# Vorlage_ATmega2560-16AU.net
KiCad netlist of a schematic drawn in EAGLE
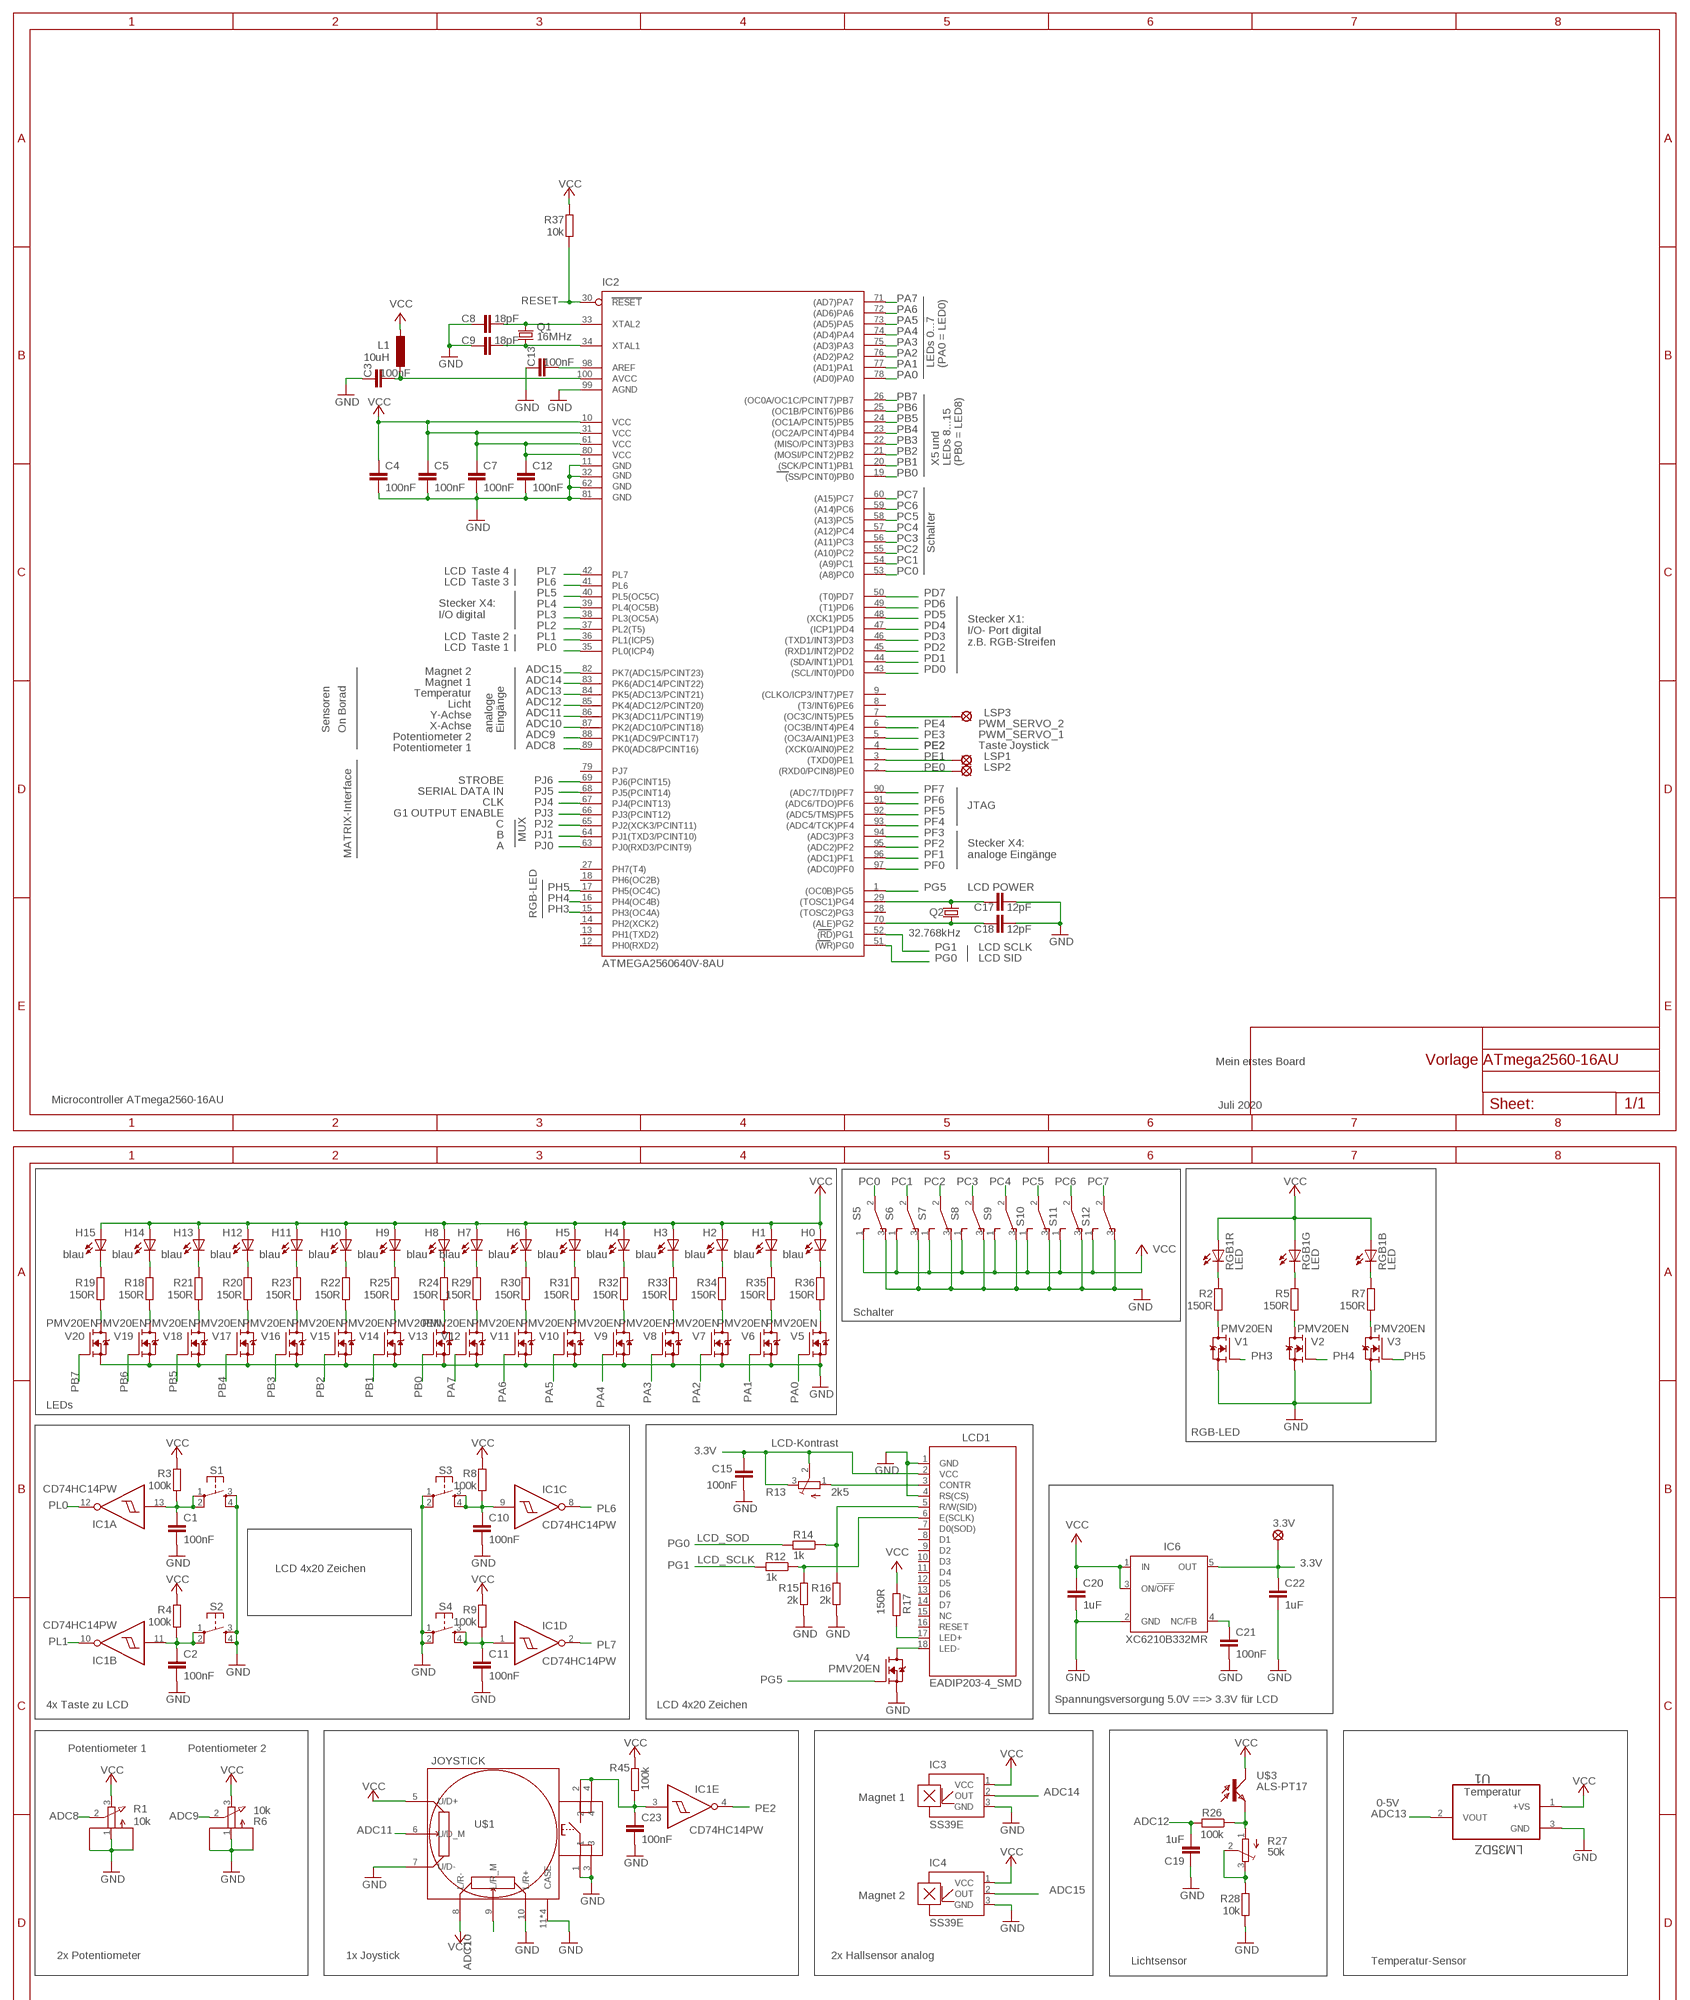
[diagram p0: schematic, sheet 1, part 1 of 2]
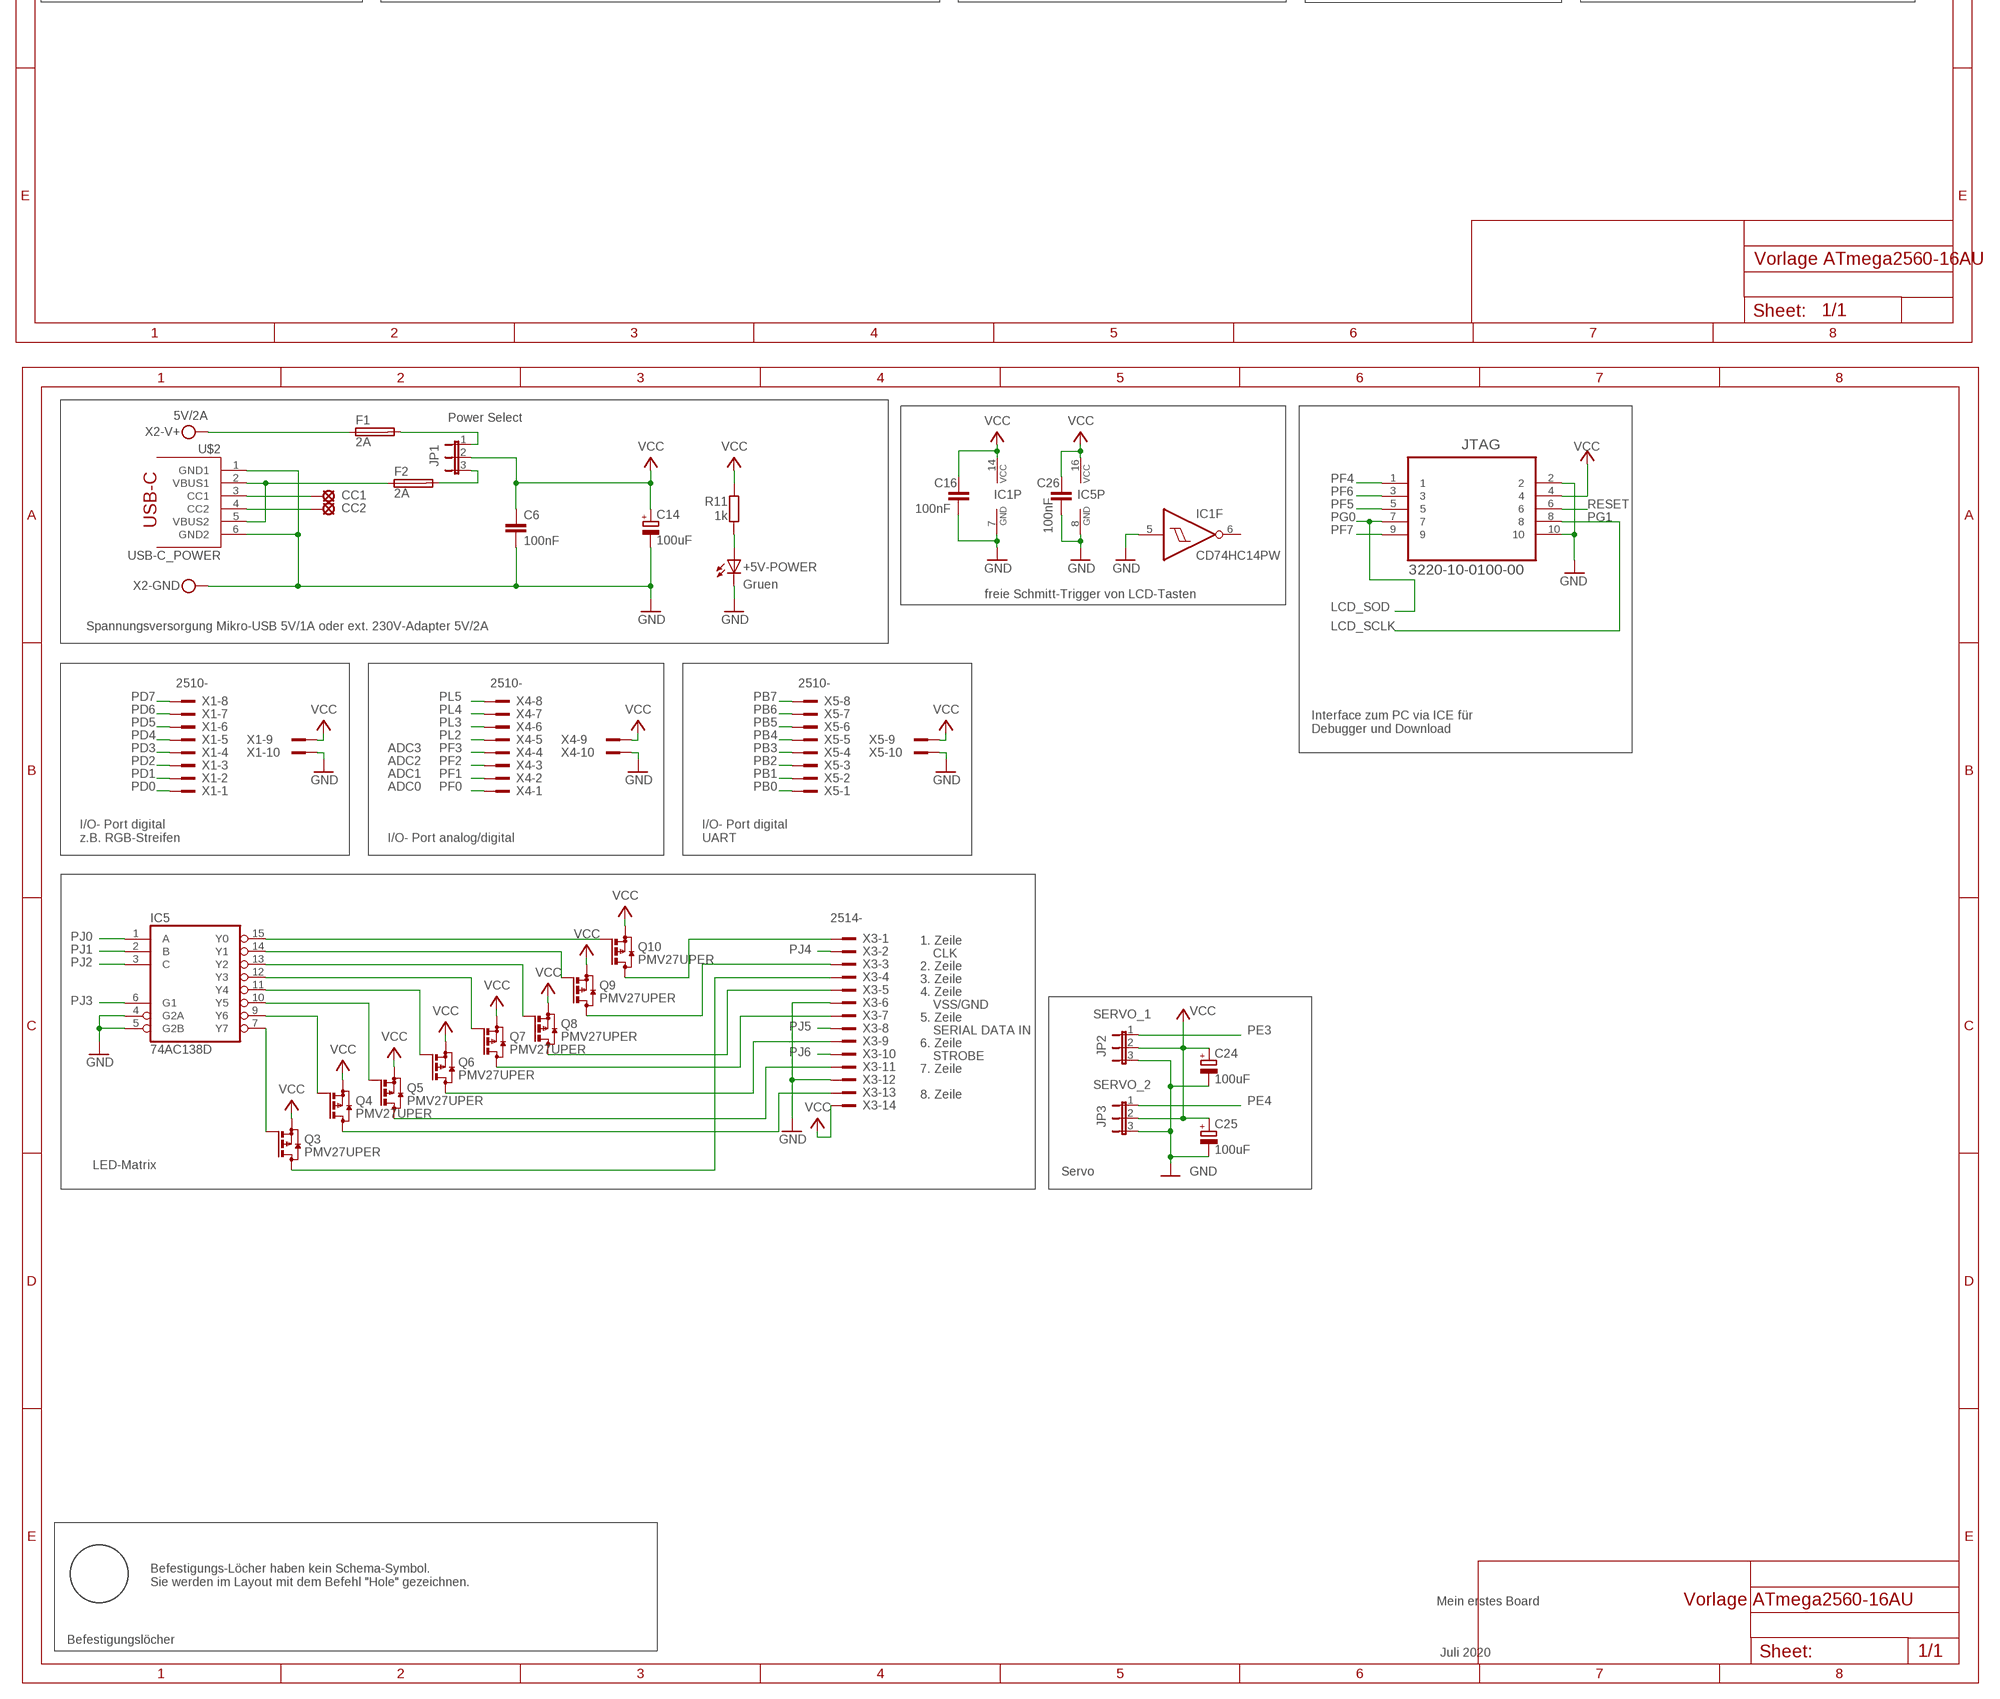
[diagram p1: schematic, sheet 1, part 2 of 2]

(export (version "E")
  (design (tool "Eeschema 10.0.6"))
  (components
    (comp (ref "+5V-POWER")
      (value "Gruen")
      (footprint "eagle-import:CHIPLED_1206")
      (libsource (lib "eagle-import") (part "LEDCHIPLED_1206"))
    )
    (comp (ref "3.3V")
      (value "3.3V")
      (footprint "eagle-import:LSP11")
      (libsource (lib "eagle-import") (part "LSP11"))
    )
    (comp (ref "C1")
      (value "100nF")
      (footprint "eagle-import:C0805")
      (libsource (lib "eagle-import") (part "C-EUC0805"))
    )
    (comp (ref "C2")
      (value "100nF")
      (footprint "eagle-import:C0805")
      (libsource (lib "eagle-import") (part "C-EUC0805"))
    )
    (comp (ref "C3")
      (value "100nF")
      (footprint "eagle-import:C0805")
      (libsource (lib "eagle-import") (part "C-EUC0805"))
    )
    (comp (ref "C4")
      (value "100nF")
      (footprint "eagle-import:C0805")
      (libsource (lib "eagle-import") (part "C-EUC0805"))
    )
    (comp (ref "C5")
      (value "100nF")
      (footprint "eagle-import:C0805")
      (libsource (lib "eagle-import") (part "C-EUC0805"))
    )
    (comp (ref "C6")
      (value "100nF")
      (footprint "eagle-import:C1206")
      (libsource (lib "eagle-import") (part "C-EUC1206"))
    )
    (comp (ref "C7")
      (value "100nF")
      (footprint "eagle-import:C0805")
      (libsource (lib "eagle-import") (part "C-EUC0805"))
    )
    (comp (ref "C8")
      (value "18pF")
      (footprint "eagle-import:C0805K")
      (libsource (lib "eagle-import") (part "C-EUC0805K"))
    )
    (comp (ref "C9")
      (value "18pF")
      (footprint "eagle-import:C0805K")
      (libsource (lib "eagle-import") (part "C-EUC0805K"))
    )
    (comp (ref "C10")
      (value "100nF")
      (footprint "eagle-import:C0805")
      (libsource (lib "eagle-import") (part "C-EUC0805"))
    )
    (comp (ref "C11")
      (value "100nF")
      (footprint "eagle-import:C0805")
      (libsource (lib "eagle-import") (part "C-EUC0805"))
    )
    (comp (ref "C12")
      (value "100nF")
      (footprint "eagle-import:C0805")
      (libsource (lib "eagle-import") (part "C-EUC0805"))
    )
    (comp (ref "C13")
      (value "100nF")
      (footprint "eagle-import:C0805")
      (libsource (lib "eagle-import") (part "C-EUC0805"))
    )
    (comp (ref "C14")
      (value "100uF")
      (footprint "eagle-import:UD-6,3X5,8_NICHICON")
      (libsource (lib "eagle-import") (part "CPOL-EUUD-6,3X8,8"))
    )
    (comp (ref "C15")
      (value "100nF")
      (footprint "eagle-import:C1206")
      (libsource (lib "eagle-import") (part "C-EUC1206"))
    )
    (comp (ref "C16")
      (value "100nF")
      (footprint "eagle-import:C1206")
      (libsource (lib "eagle-import") (part "C-EUC1206"))
    )
    (comp (ref "C17")
      (value "12pF")
      (footprint "eagle-import:C0805K")
      (libsource (lib "eagle-import") (part "C-EUC0805K"))
    )
    (comp (ref "C18")
      (value "12pF")
      (footprint "eagle-import:C0805K")
      (libsource (lib "eagle-import") (part "C-EUC0805K"))
    )
    (comp (ref "C19")
      (value "1uF")
      (footprint "eagle-import:C0805")
      (libsource (lib "eagle-import") (part "C-EUC0805"))
    )
    (comp (ref "C20")
      (value "1uF")
      (footprint "eagle-import:C0805")
      (libsource (lib "eagle-import") (part "C-EUC0805"))
    )
    (comp (ref "C21")
      (value "100nF")
      (footprint "eagle-import:C0805")
      (libsource (lib "eagle-import") (part "C-EUC0805"))
    )
    (comp (ref "C22")
      (value "1uF")
      (footprint "eagle-import:C0805")
      (libsource (lib "eagle-import") (part "C-EUC0805"))
    )
    (comp (ref "C23")
      (value "100nF")
      (footprint "eagle-import:C0805")
      (libsource (lib "eagle-import") (part "C-EUC0805"))
    )
    (comp (ref "C24")
      (value "100uF")
      (footprint "eagle-import:UD-6,3X5,8_NICHICON")
      (libsource (lib "eagle-import") (part "CPOL-EUUD-6,3X8,8"))
    )
    (comp (ref "C25")
      (value "100uF")
      (footprint "eagle-import:UD-6,3X5,8_NICHICON")
      (libsource (lib "eagle-import") (part "CPOL-EUUD-6,3X8,8"))
    )
    (comp (ref "C26")
      (value "100nF")
      (footprint "eagle-import:C1206")
      (libsource (lib "eagle-import") (part "C-EUC1206"))
    )
    (comp (ref "CC1")
      (value "LSP11")
      (footprint "eagle-import:LSP11")
      (libsource (lib "eagle-import") (part "LSP11"))
    )
    (comp (ref "CC2")
      (value "LSP11")
      (footprint "eagle-import:LSP11")
      (libsource (lib "eagle-import") (part "LSP11"))
    )
    (comp (ref "F1")
      (value "2A")
      (footprint "eagle-import:F1206")
      (libsource (lib "eagle-import") (part "195601206"))
    )
    (comp (ref "F2")
      (value "2A")
      (footprint "eagle-import:F1206")
      (libsource (lib "eagle-import") (part "195601206"))
    )
    (comp (ref "H0")
      (value "blau")
      (footprint "eagle-import:CHIPLED_1206")
      (libsource (lib "eagle-import") (part "LEDCHIPLED_1206"))
    )
    (comp (ref "H1")
      (value "blau")
      (footprint "eagle-import:CHIPLED_1206")
      (libsource (lib "eagle-import") (part "LEDCHIPLED_1206"))
    )
    (comp (ref "H2")
      (value "blau")
      (footprint "eagle-import:CHIPLED_1206")
      (libsource (lib "eagle-import") (part "LEDCHIPLED_1206"))
    )
    (comp (ref "H3")
      (value "blau")
      (footprint "eagle-import:CHIPLED_1206")
      (libsource (lib "eagle-import") (part "LEDCHIPLED_1206"))
    )
    (comp (ref "H4")
      (value "blau")
      (footprint "eagle-import:CHIPLED_1206")
      (libsource (lib "eagle-import") (part "LEDCHIPLED_1206"))
    )
    (comp (ref "H5")
      (value "blau")
      (footprint "eagle-import:CHIPLED_1206")
      (libsource (lib "eagle-import") (part "LEDCHIPLED_1206"))
    )
    (comp (ref "H6")
      (value "blau")
      (footprint "eagle-import:CHIPLED_1206")
      (libsource (lib "eagle-import") (part "LEDCHIPLED_1206"))
    )
    (comp (ref "H7")
      (value "blau")
      (footprint "eagle-import:CHIPLED_1206")
      (libsource (lib "eagle-import") (part "LEDCHIPLED_1206"))
    )
    (comp (ref "H8")
      (value "blau")
      (footprint "eagle-import:CHIPLED_1206")
      (libsource (lib "eagle-import") (part "LEDCHIPLED_1206"))
    )
    (comp (ref "H9")
      (value "blau")
      (footprint "eagle-import:CHIPLED_1206")
      (libsource (lib "eagle-import") (part "LEDCHIPLED_1206"))
    )
    (comp (ref "H10")
      (value "blau")
      (footprint "eagle-import:CHIPLED_1206")
      (libsource (lib "eagle-import") (part "LEDCHIPLED_1206"))
    )
    (comp (ref "H11")
      (value "blau")
      (footprint "eagle-import:CHIPLED_1206")
      (libsource (lib "eagle-import") (part "LEDCHIPLED_1206"))
    )
    (comp (ref "H12")
      (value "blau")
      (footprint "eagle-import:CHIPLED_1206")
      (libsource (lib "eagle-import") (part "LEDCHIPLED_1206"))
    )
    (comp (ref "H13")
      (value "blau")
      (footprint "eagle-import:CHIPLED_1206")
      (libsource (lib "eagle-import") (part "LEDCHIPLED_1206"))
    )
    (comp (ref "H14")
      (value "blau")
      (footprint "eagle-import:CHIPLED_1206")
      (libsource (lib "eagle-import") (part "LEDCHIPLED_1206"))
    )
    (comp (ref "H15")
      (value "blau")
      (footprint "eagle-import:CHIPLED_1206")
      (libsource (lib "eagle-import") (part "LEDCHIPLED_1206"))
    )
    (comp (ref "IC1")
      (value "CD74HC14PW")
      (footprint "eagle-import:SO14")
      (libsource (lib "eagle-import") (part "7414D"))
    )
    (comp (ref "IC2")
      (value "ATMEGA2560640V-8AU")
      (footprint "eagle-import:TQFP100")
      (libsource (lib "eagle-import") (part "ATMEGA2560AU640V-8"))
    )
    (comp (ref "IC3")
      (value "SS39E")
      (footprint "eagle-import:SOT23-W")
      (fields (field (name "MF") "ALLEGRO MICROSYSTEMS, INC.") (field (name "MPN") "A1301ELHLT-T"))
      (libsource (lib "eagle-import") (part "A13?LH01"))
    )
    (comp (ref "IC4")
      (value "SS39E")
      (footprint "eagle-import:SOT23-W")
      (fields (field (name "MF") "ALLEGRO MICROSYSTEMS, INC.") (field (name "MPN") "A1301ELHLT-T"))
      (libsource (lib "eagle-import") (part "A13?LH01"))
    )
    (comp (ref "IC5")
      (value "74AC138D")
      (footprint "eagle-import:SO16")
      (libsource (lib "eagle-import") (part "74138DAC"))
    )
    (comp (ref "IC6")
      (value "XC6210B332MR")
      (footprint "eagle-import:SOT23-DBV")
      (libsource (lib "eagle-import") (part "LP2985-XXDBVR"))
    )
    (comp (ref "JP1")
      (value "Power Select")
      (footprint "eagle-import:JP2")
      (libsource (lib "eagle-import") (part "JP2E"))
    )
    (comp (ref "JP2")
      (value "SERVO_1")
      (footprint "eagle-import:JP2")
      (libsource (lib "eagle-import") (part "JP2E"))
    )
    (comp (ref "JP3")
      (value "SERVO_2")
      (footprint "eagle-import:JP2")
      (libsource (lib "eagle-import") (part "JP2E"))
    )
    (comp (ref "JTAG")
      (value "3220-10-0100-00")
      (footprint "eagle-import:SAMTEC_FTS-105-01-L-D")
      (fields (field (name "MPN") "FTS-105-01-L-D"))
      (libsource (lib "eagle-import") (part "FTS-105-01-L-D"))
    )
    (comp (ref "L1")
      (value "10uH")
      (footprint "eagle-import:L2825P")
      (libsource (lib "eagle-import") (part "L-EUL2825P"))
    )
    (comp (ref "LCD1")
      (value "EADIP203-4_SMD")
      (footprint "eagle-import:EADIP203-4SMD")
      (libsource (lib "eagle-import") (part "EADIP203-4EADIP203-4SMD"))
    )
    (comp (ref "LSP1")
      (value "LSP11")
      (footprint "eagle-import:LSP11")
      (libsource (lib "eagle-import") (part "LSP11"))
    )
    (comp (ref "LSP2")
      (value "LSP11")
      (footprint "eagle-import:LSP11")
      (libsource (lib "eagle-import") (part "LSP11"))
    )
    (comp (ref "LSP3")
      (value "LSP11")
      (footprint "eagle-import:LSP11")
      (libsource (lib "eagle-import") (part "LSP11"))
    )
    (comp (ref "Q1")
      (value "16MHz")
      (footprint "eagle-import:HC49UP")
      (libsource (lib "eagle-import") (part "CRYSTALHC49UP"))
    )
    (comp (ref "Q2")
      (value "32.768kHz")
      (footprint "eagle-import:TC38H")
      (libsource (lib "eagle-import") (part "CRYSTALTC38H"))
    )
    (comp (ref "Q3")
      (value "PMV27UPER")
      (footprint "eagle-import:SOT23")
      (libsource (lib "eagle-import") (part "BSS84"))
    )
    (comp (ref "Q4")
      (value "PMV27UPER")
      (footprint "eagle-import:SOT23")
      (libsource (lib "eagle-import") (part "BSS84"))
    )
    (comp (ref "Q5")
      (value "PMV27UPER")
      (footprint "eagle-import:SOT23")
      (libsource (lib "eagle-import") (part "BSS84"))
    )
    (comp (ref "Q6")
      (value "PMV27UPER")
      (footprint "eagle-import:SOT23")
      (libsource (lib "eagle-import") (part "BSS84"))
    )
    (comp (ref "Q7")
      (value "PMV27UPER")
      (footprint "eagle-import:SOT23")
      (libsource (lib "eagle-import") (part "BSS84"))
    )
    (comp (ref "Q8")
      (value "PMV27UPER")
      (footprint "eagle-import:SOT23")
      (libsource (lib "eagle-import") (part "BSS84"))
    )
    (comp (ref "Q9")
      (value "PMV27UPER")
      (footprint "eagle-import:SOT23")
      (libsource (lib "eagle-import") (part "BSS84"))
    )
    (comp (ref "Q10")
      (value "PMV27UPER")
      (footprint "eagle-import:SOT23")
      (libsource (lib "eagle-import") (part "BSS84"))
    )
    (comp (ref "R1")
      (value "10k")
      (footprint "eagle-import:EVUF")
      (libsource (lib "eagle-import") (part "EVUA"))
    )
    (comp (ref "R2")
      (value "150R")
      (footprint "eagle-import:R0805")
      (libsource (lib "eagle-import") (part "R-EU_R0805"))
    )
    (comp (ref "R3")
      (value "100k")
      (footprint "eagle-import:R0805")
      (libsource (lib "eagle-import") (part "R-EU_R0805"))
    )
    (comp (ref "R4")
      (value "100k")
      (footprint "eagle-import:R0805")
      (libsource (lib "eagle-import") (part "R-EU_R0805"))
    )
    (comp (ref "R5")
      (value "150R")
      (footprint "eagle-import:R0805")
      (libsource (lib "eagle-import") (part "R-EU_R0805"))
    )
    (comp (ref "R6")
      (value "10k")
      (footprint "eagle-import:EVUF")
      (libsource (lib "eagle-import") (part "EVUA"))
    )
    (comp (ref "R7")
      (value "150R")
      (footprint "eagle-import:R0805")
      (libsource (lib "eagle-import") (part "R-EU_R0805"))
    )
    (comp (ref "R8")
      (value "100k")
      (footprint "eagle-import:R0805")
      (libsource (lib "eagle-import") (part "R-EU_R0805"))
    )
    (comp (ref "R9")
      (value "100k")
      (footprint "eagle-import:R0805")
      (libsource (lib "eagle-import") (part "R-EU_R0805"))
    )
    (comp (ref "R11")
      (value "1k")
      (footprint "eagle-import:R0805")
      (libsource (lib "eagle-import") (part "R-EU_R0805"))
    )
    (comp (ref "R12")
      (value "1k")
      (footprint "eagle-import:R0805")
      (libsource (lib "eagle-import") (part "R-EU_R0805"))
    )
    (comp (ref "R13")
      (value "2k5")
      (footprint "eagle-import:3223G")
      (libsource (lib "eagle-import") (part "TRIM_EU-3223G"))
    )
    (comp (ref "R14")
      (value "1k")
      (footprint "eagle-import:R0805")
      (libsource (lib "eagle-import") (part "R-EU_R0805"))
    )
    (comp (ref "R15")
      (value "2k")
      (footprint "eagle-import:R0805")
      (libsource (lib "eagle-import") (part "R-EU_R0805"))
    )
    (comp (ref "R16")
      (value "2k")
      (footprint "eagle-import:R0805")
      (libsource (lib "eagle-import") (part "R-EU_R0805"))
    )
    (comp (ref "R17")
      (value "150R")
      (footprint "eagle-import:R1206")
      (libsource (lib "eagle-import") (part "R-EU_R1206"))
    )
    (comp (ref "R18")
      (value "150R")
      (footprint "eagle-import:R0805")
      (libsource (lib "eagle-import") (part "R-EU_R0805"))
    )
    (comp (ref "R19")
      (value "150R")
      (footprint "eagle-import:R0805")
      (libsource (lib "eagle-import") (part "R-EU_R0805"))
    )
    (comp (ref "R20")
      (value "150R")
      (footprint "eagle-import:R0805")
      (libsource (lib "eagle-import") (part "R-EU_R0805"))
    )
    (comp (ref "R21")
      (value "150R")
      (footprint "eagle-import:R0805")
      (libsource (lib "eagle-import") (part "R-EU_R0805"))
    )
    (comp (ref "R22")
      (value "150R")
      (footprint "eagle-import:R0805")
      (libsource (lib "eagle-import") (part "R-EU_R0805"))
    )
    (comp (ref "R23")
      (value "150R")
      (footprint "eagle-import:R0805")
      (libsource (lib "eagle-import") (part "R-EU_R0805"))
    )
    (comp (ref "R24")
      (value "150R")
      (footprint "eagle-import:R0805")
      (libsource (lib "eagle-import") (part "R-EU_R0805"))
    )
    (comp (ref "R25")
      (value "150R")
      (footprint "eagle-import:R0805")
      (libsource (lib "eagle-import") (part "R-EU_R0805"))
    )
    (comp (ref "R26")
      (value "100k")
      (footprint "eagle-import:R0805")
      (libsource (lib "eagle-import") (part "R-EU_R0805"))
    )
    (comp (ref "R27")
      (value "50k")
      (footprint "eagle-import:3223G")
      (libsource (lib "eagle-import") (part "TRIM_EU-3223G"))
    )
    (comp (ref "R28")
      (value "10k")
      (footprint "eagle-import:R0805")
      (libsource (lib "eagle-import") (part "R-EU_R0805"))
    )
    (comp (ref "R29")
      (value "150R")
      (footprint "eagle-import:R0805")
      (libsource (lib "eagle-import") (part "R-EU_R0805"))
    )
    (comp (ref "R30")
      (value "150R")
      (footprint "eagle-import:R0805")
      (libsource (lib "eagle-import") (part "R-EU_R0805"))
    )
    (comp (ref "R31")
      (value "150R")
      (footprint "eagle-import:R0805")
      (libsource (lib "eagle-import") (part "R-EU_R0805"))
    )
    (comp (ref "R32")
      (value "150R")
      (footprint "eagle-import:R0805")
      (libsource (lib "eagle-import") (part "R-EU_R0805"))
    )
    (comp (ref "R33")
      (value "150R")
      (footprint "eagle-import:R0805")
      (libsource (lib "eagle-import") (part "R-EU_R0805"))
    )
    (comp (ref "R34")
      (value "150R")
      (footprint "eagle-import:R0805")
      (libsource (lib "eagle-import") (part "R-EU_R0805"))
    )
    (comp (ref "R35")
      (value "150R")
      (footprint "eagle-import:R0805")
      (libsource (lib "eagle-import") (part "R-EU_R0805"))
    )
    (comp (ref "R36")
      (value "150R")
      (footprint "eagle-import:R0805")
      (libsource (lib "eagle-import") (part "R-EU_R0805"))
    )
    (comp (ref "R37")
      (value "10k")
      (footprint "eagle-import:R0805")
      (libsource (lib "eagle-import") (part "R-EU_R0805"))
    )
    (comp (ref "R45")
      (value "100k")
      (footprint "eagle-import:R0805")
      (libsource (lib "eagle-import") (part "R-EU_R0805"))
    )
    (comp (ref "RGB1")
      (value "LED")
      (footprint "eagle-import:LED_MIT_DIFUSOR")
      (libsource (lib "eagle-import") (part "GM5WA94310AMIT_DIFUSOR"))
    )
    (comp (ref "S1")
      (value "TS42_4PAD")
      (footprint "eagle-import:TS42_4PAD")
      (libsource (lib "eagle-import") (part "TS42_4PAD"))
    )
    (comp (ref "S2")
      (value "TS42_4PAD")
      (footprint "eagle-import:TS42_4PAD")
      (libsource (lib "eagle-import") (part "TS42_4PAD"))
    )
    (comp (ref "S3")
      (value "TS42_4PAD")
      (footprint "eagle-import:TS42_4PAD")
      (libsource (lib "eagle-import") (part "TS42_4PAD"))
    )
    (comp (ref "S4")
      (value "TS42_4PAD")
      (footprint "eagle-import:TS42_4PAD")
      (libsource (lib "eagle-import") (part "TS42_4PAD"))
    )
    (comp (ref "S5")
      (value "TL36POSPDT_5MM")
      (footprint "eagle-import:SPDT_5MM")
      (libsource (lib "eagle-import") (part "TL36POSPDT_5MM"))
    )
    (comp (ref "S6")
      (value "TL36POSPDT_5MM")
      (footprint "eagle-import:SPDT_5MM")
      (libsource (lib "eagle-import") (part "TL36POSPDT_5MM"))
    )
    (comp (ref "S7")
      (value "TL36POSPDT_5MM")
      (footprint "eagle-import:SPDT_5MM")
      (libsource (lib "eagle-import") (part "TL36POSPDT_5MM"))
    )
    (comp (ref "S8")
      (value "TL36POSPDT_5MM")
      (footprint "eagle-import:SPDT_5MM")
      (libsource (lib "eagle-import") (part "TL36POSPDT_5MM"))
    )
    (comp (ref "S9")
      (value "TL36POSPDT_5MM")
      (footprint "eagle-import:SPDT_5MM")
      (libsource (lib "eagle-import") (part "TL36POSPDT_5MM"))
    )
    (comp (ref "S10")
      (value "TL36POSPDT_5MM")
      (footprint "eagle-import:SPDT_5MM")
      (libsource (lib "eagle-import") (part "TL36POSPDT_5MM"))
    )
    (comp (ref "S11")
      (value "TL36POSPDT_5MM")
      (footprint "eagle-import:SPDT_5MM")
      (libsource (lib "eagle-import") (part "TL36POSPDT_5MM"))
    )
    (comp (ref "S12")
      (value "TL36POSPDT_5MM")
      (footprint "eagle-import:SPDT_5MM")
      (libsource (lib "eagle-import") (part "TL36POSPDT_5MM"))
    )
    (comp (ref "U$1")
      (value "JOYSTICK")
      (footprint "eagle-import:RKJXV1224005")
      (libsource (lib "eagle-import") (part "JOYSTICK"))
    )
    (comp (ref "U$2")
      (value "USB-C_POWER")
      (footprint "eagle-import:USB-C")
      (libsource (lib "eagle-import") (part "USB-C_POWER"))
    )
    (comp (ref "U$3")
      (value "ALS-PT17")
      (footprint "eagle-import:SOD232-W")
      (libsource (lib "eagle-import") (part "ALS-PT17-51C"))
    )
    (comp (ref "U1")
      (value "LM35DZ")
      (footprint "eagle-import:TO127P254X495-3P")
      (libsource (lib "eagle-import") (part "LM35DZ"))
    )
    (comp (ref "V1")
      (value "PMV20EN")
      (footprint "eagle-import:SOT23")
      (libsource (lib "eagle-import") (part "BSS138"))
    )
    (comp (ref "V2")
      (value "PMV20EN")
      (footprint "eagle-import:SOT23")
      (libsource (lib "eagle-import") (part "BSS138"))
    )
    (comp (ref "V3")
      (value "PMV20EN")
      (footprint "eagle-import:SOT23")
      (libsource (lib "eagle-import") (part "BSS138"))
    )
    (comp (ref "V4")
      (value "PMV20EN")
      (footprint "eagle-import:SOT23")
      (libsource (lib "eagle-import") (part "BSS138"))
    )
    (comp (ref "V5")
      (value "PMV20EN")
      (footprint "eagle-import:SOT23")
      (libsource (lib "eagle-import") (part "BSS138"))
    )
    (comp (ref "V6")
      (value "PMV20EN")
      (footprint "eagle-import:SOT23")
      (libsource (lib "eagle-import") (part "BSS138"))
    )
    (comp (ref "V7")
      (value "PMV20EN")
      (footprint "eagle-import:SOT23")
      (libsource (lib "eagle-import") (part "BSS138"))
    )
    (comp (ref "V8")
      (value "PMV20EN")
      (footprint "eagle-import:SOT23")
      (libsource (lib "eagle-import") (part "BSS138"))
    )
    (comp (ref "V9")
      (value "PMV20EN")
      (footprint "eagle-import:SOT23")
      (libsource (lib "eagle-import") (part "BSS138"))
    )
    (comp (ref "V10")
      (value "PMV20EN")
      (footprint "eagle-import:SOT23")
      (libsource (lib "eagle-import") (part "BSS138"))
    )
    (comp (ref "V11")
      (value "PMV20EN")
      (footprint "eagle-import:SOT23")
      (libsource (lib "eagle-import") (part "BSS138"))
    )
    (comp (ref "V12")
      (value "PMV20EN")
      (footprint "eagle-import:SOT23")
      (libsource (lib "eagle-import") (part "BSS138"))
    )
    (comp (ref "V13")
      (value "PMV20EN")
      (footprint "eagle-import:SOT23")
      (libsource (lib "eagle-import") (part "BSS138"))
    )
    (comp (ref "V14")
      (value "PMV20EN")
      (footprint "eagle-import:SOT23")
      (libsource (lib "eagle-import") (part "BSS138"))
    )
    (comp (ref "V15")
      (value "PMV20EN")
      (footprint "eagle-import:SOT23")
      (libsource (lib "eagle-import") (part "BSS138"))
    )
    (comp (ref "V16")
      (value "PMV20EN")
      (footprint "eagle-import:SOT23")
      (libsource (lib "eagle-import") (part "BSS138"))
    )
    (comp (ref "V17")
      (value "PMV20EN")
      (footprint "eagle-import:SOT23")
      (libsource (lib "eagle-import") (part "BSS138"))
    )
    (comp (ref "V18")
      (value "PMV20EN")
      (footprint "eagle-import:SOT23")
      (libsource (lib "eagle-import") (part "BSS138"))
    )
    (comp (ref "V19")
      (value "PMV20EN")
      (footprint "eagle-import:SOT23")
      (libsource (lib "eagle-import") (part "BSS138"))
    )
    (comp (ref "V20")
      (value "PMV20EN")
      (footprint "eagle-import:SOT23")
      (libsource (lib "eagle-import") (part "BSS138"))
    )
    (comp (ref "X1")
      (value "2510-")
      (footprint "eagle-import:PAK100_2500-10")
      (fields (field (name "MF") "3M") (field (name "MPN") "2510-6002UB"))
      (libsource (lib "eagle-import") (part "2510-"))
    )
    (comp (ref "X2")
      (value "+5V")
      (footprint "eagle-import:MKDSN1,5_2-5,08")
      (fields (field (name "MPN") "MKDSN 1,5/2-5.08"))
      (libsource (lib "eagle-import") (part "MKDSN1,5/2-5,08"))
    )
    (comp (ref "X3")
      (value "2514-")
      (footprint "eagle-import:PAK100_2500-14")
      (libsource (lib "eagle-import") (part "2514-"))
    )
    (comp (ref "X4")
      (value "2510-")
      (footprint "eagle-import:PAK100_2500-10")
      (fields (field (name "MF") "3M") (field (name "MPN") "2510-6002UB"))
      (libsource (lib "eagle-import") (part "2510-"))
    )
    (comp (ref "X5")
      (value "2510-")
      (footprint "eagle-import:PAK100_2500-10")
      (fields (field (name "MF") "3M") (field (name "MPN") "2510-6002UB"))
      (libsource (lib "eagle-import") (part "2510-"))
    )
  )
  (nets
    (net (code "1") (name "/3.3V") (class "Default")
      (node (ref "3.3V") (pin "MP") (pinfunction "MP_MP") (pintype "passive"))
      (node (ref "C15") (pin "1") (pinfunction "1_1") (pintype "passive"))
      (node (ref "C22") (pin "1") (pinfunction "1_1") (pintype "passive"))
      (node (ref "IC6") (pin "5") (pinfunction "OUT_5") (pintype "passive"))
      (node (ref "LCD1") (pin "2") (pinfunction "VCC_2") (pintype "passive"))
      (node (ref "R13") (pin "2") (pinfunction "S_2") (pintype "passive"))
      (node (ref "R13") (pin "3") (pinfunction "E_3") (pintype "passive"))
    )
    (net (code "2") (name "/ADC8") (class "Default")
      (node (ref "IC2") (pin "89") (pinfunction "PK0(ADC8/PCINT16)_89") (pintype "bidirectional"))
      (node (ref "R1") (pin "2") (pinfunction "S_2") (pintype "passive"))
    )
    (net (code "3") (name "/ADC9") (class "Default")
      (node (ref "IC2") (pin "88") (pinfunction "PK1(ADC9/PCINT17)_88") (pintype "bidirectional"))
      (node (ref "R6") (pin "2") (pinfunction "S_2") (pintype "passive"))
    )
    (net (code "4") (name "/ADC10") (class "Default")
      (node (ref "IC2") (pin "87") (pinfunction "PK2(ADC10/PCINT18)_87") (pintype "bidirectional"))
      (node (ref "U$1") (pin "9") (pinfunction "L/R_M_9") (pintype "bidirectional"))
    )
    (net (code "5") (name "/ADC11") (class "Default")
      (node (ref "IC2") (pin "86") (pinfunction "PK3(ADC11/PCINT19)_86") (pintype "bidirectional"))
      (node (ref "U$1") (pin "6") (pinfunction "U/D_M_6") (pintype "bidirectional"))
    )
    (net (code "6") (name "/ADC12") (class "Default")
      (node (ref "C19") (pin "2") (pinfunction "2_2") (pintype "passive"))
      (node (ref "IC2") (pin "85") (pinfunction "PK4(ADC12/PCINT20)_85") (pintype "bidirectional"))
      (node (ref "R26") (pin "2") (pinfunction "2_2") (pintype "passive"))
    )
    (net (code "7") (name "/ADC13") (class "Default")
      (node (ref "IC2") (pin "84") (pinfunction "PK5(ADC13/PCINT21)_84") (pintype "bidirectional"))
      (node (ref "U1") (pin "2") (pinfunction "VOUT_2") (pintype "output"))
    )
    (net (code "8") (name "/ADC14") (class "Default")
      (node (ref "IC2") (pin "83") (pinfunction "PK6(ADC14/PCINT22)_83") (pintype "bidirectional"))
      (node (ref "IC3") (pin "2") (pinfunction "OUT_2") (pintype "output"))
    )
    (net (code "9") (name "/ADC15") (class "Default")
      (node (ref "IC2") (pin "82") (pinfunction "PK7(ADC15/PCINT23)_82") (pintype "bidirectional"))
      (node (ref "IC4") (pin "2") (pinfunction "OUT_2") (pintype "output"))
    )
    (net (code "10") (name "/PA0") (class "Default")
      (node (ref "IC2") (pin "78") (pinfunction "(AD0)PA0_78") (pintype "bidirectional"))
      (node (ref "V5") (pin "1") (pinfunction "G_1") (pintype "passive"))
    )
    (net (code "11") (name "/PA1") (class "Default")
      (node (ref "IC2") (pin "77") (pinfunction "(AD1)PA1_77") (pintype "bidirectional"))
      (node (ref "V6") (pin "1") (pinfunction "G_1") (pintype "passive"))
    )
    (net (code "12") (name "/PA2") (class "Default")
      (node (ref "IC2") (pin "76") (pinfunction "(AD2)PA2_76") (pintype "bidirectional"))
      (node (ref "V7") (pin "1") (pinfunction "G_1") (pintype "passive"))
    )
    (net (code "13") (name "/PA3") (class "Default")
      (node (ref "IC2") (pin "75") (pinfunction "(AD3)PA3_75") (pintype "bidirectional"))
      (node (ref "V8") (pin "1") (pinfunction "G_1") (pintype "passive"))
    )
    (net (code "14") (name "/PA4") (class "Default")
      (node (ref "IC2") (pin "74") (pinfunction "(AD4)PA4_74") (pintype "bidirectional"))
      (node (ref "V9") (pin "1") (pinfunction "G_1") (pintype "passive"))
    )
    (net (code "15") (name "/PA5") (class "Default")
      (node (ref "IC2") (pin "73") (pinfunction "(AD5)PA5_73") (pintype "bidirectional"))
      (node (ref "V10") (pin "1") (pinfunction "G_1") (pintype "passive"))
    )
    (net (code "16") (name "/PA6") (class "Default")
      (node (ref "IC2") (pin "72") (pinfunction "(AD6)PA6_72") (pintype "bidirectional"))
      (node (ref "V11") (pin "1") (pinfunction "G_1") (pintype "passive"))
    )
    (net (code "17") (name "/PA7") (class "Default")
      (node (ref "IC2") (pin "71") (pinfunction "(AD7)PA7_71") (pintype "bidirectional"))
      (node (ref "V12") (pin "1") (pinfunction "G_1") (pintype "passive"))
    )
    (net (code "18") (name "/PB0") (class "Default")
      (node (ref "IC2") (pin "19") (pinfunction "(SS/PCINT0)PB0_19") (pintype "bidirectional"))
      (node (ref "V13") (pin "1") (pinfunction "G_1") (pintype "passive"))
      (node (ref "X5") (pin "1") (pinfunction "KL_1") (pintype "passive"))
    )
    (net (code "19") (name "/PB1") (class "Default")
      (node (ref "IC2") (pin "20") (pinfunction "(SCK/PCINT1)PB1_20") (pintype "bidirectional"))
      (node (ref "V14") (pin "1") (pinfunction "G_1") (pintype "passive"))
      (node (ref "X5") (pin "2") (pinfunction "KL_2") (pintype "passive"))
    )
    (net (code "20") (name "/PB2") (class "Default")
      (node (ref "IC2") (pin "21") (pinfunction "(MOSI/PCINT2)PB2_21") (pintype "bidirectional"))
      (node (ref "V15") (pin "1") (pinfunction "G_1") (pintype "passive"))
      (node (ref "X5") (pin "3") (pinfunction "KL_3") (pintype "passive"))
    )
    (net (code "21") (name "/PB3") (class "Default")
      (node (ref "IC2") (pin "22") (pinfunction "(MISO/PCINT3)PB3_22") (pintype "bidirectional"))
      (node (ref "V16") (pin "1") (pinfunction "G_1") (pintype "passive"))
      (node (ref "X5") (pin "4") (pinfunction "KL_4") (pintype "passive"))
    )
    (net (code "22") (name "/PB4") (class "Default")
      (node (ref "IC2") (pin "23") (pinfunction "(OC2A/PCINT4)PB4_23") (pintype "bidirectional"))
      (node (ref "V17") (pin "1") (pinfunction "G_1") (pintype "passive"))
      (node (ref "X5") (pin "5") (pinfunction "KL_5") (pintype "passive"))
    )
    (net (code "23") (name "/PB5") (class "Default")
      (node (ref "IC2") (pin "24") (pinfunction "(OC1A/PCINT5)PB5_24") (pintype "bidirectional"))
      (node (ref "V18") (pin "1") (pinfunction "G_1") (pintype "passive"))
      (node (ref "X5") (pin "6") (pinfunction "KL_6") (pintype "passive"))
    )
    (net (code "24") (name "/PB6") (class "Default")
      (node (ref "IC2") (pin "25") (pinfunction "(OC1B/PCINT6)PB6_25") (pintype "bidirectional"))
      (node (ref "V19") (pin "1") (pinfunction "G_1") (pintype "passive"))
      (node (ref "X5") (pin "7") (pinfunction "KL_7") (pintype "passive"))
    )
    (net (code "25") (name "/PB7") (class "Default")
      (node (ref "IC2") (pin "26") (pinfunction "(OC0A/OC1C/PCINT7)PB7_26") (pintype "bidirectional"))
      (node (ref "V20") (pin "1") (pinfunction "G_1") (pintype "passive"))
      (node (ref "X5") (pin "8") (pinfunction "KL_8") (pintype "passive"))
    )
    (net (code "26") (name "/PC0") (class "Default")
      (node (ref "IC2") (pin "53") (pinfunction "(A8)PC0_53") (pintype "bidirectional"))
      (node (ref "S5") (pin "2") (pinfunction "P_2") (pintype "passive"))
    )
    (net (code "27") (name "/PC1") (class "Default")
      (node (ref "IC2") (pin "54") (pinfunction "(A9)PC1_54") (pintype "bidirectional"))
      (node (ref "S6") (pin "2") (pinfunction "P_2") (pintype "passive"))
    )
    (net (code "28") (name "/PC2") (class "Default")
      (node (ref "IC2") (pin "55") (pinfunction "(A10)PC2_55") (pintype "bidirectional"))
      (node (ref "S7") (pin "2") (pinfunction "P_2") (pintype "passive"))
    )
    (net (code "29") (name "/PC3") (class "Default")
      (node (ref "IC2") (pin "56") (pinfunction "(A11)PC3_56") (pintype "bidirectional"))
      (node (ref "S8") (pin "2") (pinfunction "P_2") (pintype "passive"))
    )
    (net (code "30") (name "/PC4") (class "Default")
      (node (ref "IC2") (pin "57") (pinfunction "(A12)PC4_57") (pintype "bidirectional"))
      (node (ref "S9") (pin "2") (pinfunction "P_2") (pintype "passive"))
    )
    (net (code "31") (name "/PC5") (class "Default")
      (node (ref "IC2") (pin "58") (pinfunction "(A13)PC5_58") (pintype "bidirectional"))
      (node (ref "S10") (pin "2") (pinfunction "P_2") (pintype "passive"))
    )
    (net (code "32") (name "/PC6") (class "Default")
      (node (ref "IC2") (pin "59") (pinfunction "(A14)PC6_59") (pintype "bidirectional"))
      (node (ref "S11") (pin "2") (pinfunction "P_2") (pintype "passive"))
    )
    (net (code "33") (name "/PC7") (class "Default")
      (node (ref "IC2") (pin "60") (pinfunction "(A15)PC7_60") (pintype "bidirectional"))
      (node (ref "S12") (pin "2") (pinfunction "P_2") (pintype "passive"))
    )
    (net (code "34") (name "/PD0") (class "Default")
      (node (ref "IC2") (pin "43") (pinfunction "(SCL/INT0)PD0_43") (pintype "bidirectional"))
      (node (ref "X1") (pin "1") (pinfunction "KL_1") (pintype "passive"))
    )
    (net (code "35") (name "/PD1") (class "Default")
      (node (ref "IC2") (pin "44") (pinfunction "(SDA/INT1)PD1_44") (pintype "bidirectional"))
      (node (ref "X1") (pin "2") (pinfunction "KL_2") (pintype "passive"))
    )
    (net (code "36") (name "/PD2") (class "Default")
      (node (ref "IC2") (pin "45") (pinfunction "(RXD1/INT2)PD2_45") (pintype "bidirectional"))
      (node (ref "X1") (pin "3") (pinfunction "KL_3") (pintype "passive"))
    )
    (net (code "37") (name "/PD3") (class "Default")
      (node (ref "IC2") (pin "46") (pinfunction "(TXD1/INT3)PD3_46") (pintype "bidirectional"))
      (node (ref "X1") (pin "4") (pinfunction "KL_4") (pintype "passive"))
    )
    (net (code "38") (name "/PD4") (class "Default")
      (node (ref "IC2") (pin "47") (pinfunction "(ICP1)PD4_47") (pintype "bidirectional"))
      (node (ref "X1") (pin "5") (pinfunction "KL_5") (pintype "passive"))
    )
    (net (code "39") (name "/PD5") (class "Default")
      (node (ref "IC2") (pin "48") (pinfunction "(XCK1)PD5_48") (pintype "bidirectional"))
      (node (ref "X1") (pin "6") (pinfunction "KL_6") (pintype "passive"))
    )
    (net (code "40") (name "/PD6") (class "Default")
      (node (ref "IC2") (pin "49") (pinfunction "(T1)PD6_49") (pintype "bidirectional"))
      (node (ref "X1") (pin "7") (pinfunction "KL_7") (pintype "passive"))
    )
    (net (code "41") (name "/PD7") (class "Default")
      (node (ref "IC2") (pin "50") (pinfunction "(T0)PD7_50") (pintype "bidirectional"))
      (node (ref "X1") (pin "8") (pinfunction "KL_8") (pintype "passive"))
    )
    (net (code "42") (name "/PE0") (class "Default")
      (node (ref "IC2") (pin "2") (pinfunction "(RXD0/PCIN8)PE0_2") (pintype "bidirectional"))
      (node (ref "LSP2") (pin "MP") (pinfunction "MP_MP") (pintype "passive"))
    )
    (net (code "43") (name "/PE1") (class "Default")
      (node (ref "IC2") (pin "3") (pinfunction "(TXD0)PE1_3") (pintype "bidirectional"))
      (node (ref "LSP1") (pin "MP") (pinfunction "MP_MP") (pintype "passive"))
    )
    (net (code "44") (name "/PE2") (class "Default")
      (node (ref "IC1") (pin "4") (pinfunction "O_4") (pintype "output"))
      (node (ref "IC2") (pin "4") (pinfunction "(XCK0/AIN0)PE2_4") (pintype "bidirectional"))
    )
    (net (code "45") (name "/PE3") (class "Default")
      (node (ref "IC2") (pin "5") (pinfunction "(OC3A/AIN1)PE3_5") (pintype "bidirectional"))
      (node (ref "JP2") (pin "1") (pinfunction "1_1") (pintype "passive"))
    )
    (net (code "46") (name "/PE4") (class "Default")
      (node (ref "IC2") (pin "6") (pinfunction "(OC3B/INT4)PE4_6") (pintype "bidirectional"))
      (node (ref "JP3") (pin "1") (pinfunction "1_1") (pintype "passive"))
    )
    (net (code "47") (name "/PF0") (class "Default")
      (node (ref "IC2") (pin "97") (pinfunction "(ADC0)PF0_97") (pintype "bidirectional"))
      (node (ref "X4") (pin "1") (pinfunction "KL_1") (pintype "passive"))
    )
    (net (code "48") (name "/PF1") (class "Default")
      (node (ref "IC2") (pin "96") (pinfunction "(ADC1)PF1_96") (pintype "bidirectional"))
      (node (ref "X4") (pin "2") (pinfunction "KL_2") (pintype "passive"))
    )
    (net (code "49") (name "/PF2") (class "Default")
      (node (ref "IC2") (pin "95") (pinfunction "(ADC2)PF2_95") (pintype "bidirectional"))
      (node (ref "X4") (pin "3") (pinfunction "KL_3") (pintype "passive"))
    )
    (net (code "50") (name "/PF3") (class "Default")
      (node (ref "IC2") (pin "94") (pinfunction "(ADC3)PF3_94") (pintype "bidirectional"))
      (node (ref "X4") (pin "4") (pinfunction "KL_4") (pintype "passive"))
    )
    (net (code "51") (name "/PF4") (class "Default")
      (node (ref "IC2") (pin "93") (pinfunction "(ADC4/TCK)PF4_93") (pintype "bidirectional"))
      (node (ref "JTAG") (pin "1") (pinfunction "1_1") (pintype "passive"))
    )
    (net (code "52") (name "/PF5") (class "Default")
      (node (ref "IC2") (pin "92") (pinfunction "(ADC5/TMS)PF5_92") (pintype "bidirectional"))
      (node (ref "JTAG") (pin "5") (pinfunction "5_5") (pintype "passive"))
    )
    (net (code "53") (name "/PF6") (class "Default")
      (node (ref "IC2") (pin "91") (pinfunction "(ADC6/TDO)PF6_91") (pintype "bidirectional"))
      (node (ref "JTAG") (pin "3") (pinfunction "3_3") (pintype "passive"))
    )
    (net (code "54") (name "/PF7") (class "Default")
      (node (ref "IC2") (pin "90") (pinfunction "(ADC7/TDI)PF7_90") (pintype "bidirectional"))
      (node (ref "JTAG") (pin "9") (pinfunction "9_9") (pintype "passive"))
    )
    (net (code "55") (name "/PG0") (class "Default")
      (node (ref "IC2") (pin "51") (pinfunction "(WR)PG0_51") (pintype "bidirectional"))
      (node (ref "JTAG") (pin "7") (pinfunction "7_7") (pintype "passive"))
      (node (ref "R14") (pin "2") (pinfunction "2_2") (pintype "passive"))
    )
    (net (code "56") (name "/PG1") (class "Default")
      (node (ref "IC2") (pin "52") (pinfunction "(RD)PG1_52") (pintype "bidirectional"))
      (node (ref "JTAG") (pin "8") (pinfunction "8_8") (pintype "passive"))
      (node (ref "R12") (pin "2") (pinfunction "2_2") (pintype "passive"))
    )
    (net (code "57") (name "/PG5") (class "Default")
      (node (ref "IC2") (pin "1") (pinfunction "(OC0B)PG5_1") (pintype "bidirectional"))
      (node (ref "V4") (pin "1") (pinfunction "G_1") (pintype "passive"))
    )
    (net (code "58") (name "/PH3") (class "Default")
      (node (ref "IC2") (pin "15") (pinfunction "PH3(OC4A)_15") (pintype "bidirectional"))
      (node (ref "V1") (pin "1") (pinfunction "G_1") (pintype "passive"))
    )
    (net (code "59") (name "/PH4") (class "Default")
      (node (ref "IC2") (pin "16") (pinfunction "PH4(OC4B)_16") (pintype "bidirectional"))
      (node (ref "V2") (pin "1") (pinfunction "G_1") (pintype "passive"))
    )
    (net (code "60") (name "/PH5") (class "Default")
      (node (ref "IC2") (pin "17") (pinfunction "PH5(OC4C)_17") (pintype "bidirectional"))
      (node (ref "V3") (pin "1") (pinfunction "G_1") (pintype "passive"))
    )
    (net (code "61") (name "/PJ0") (class "Default")
      (node (ref "IC2") (pin "63") (pinfunction "PJ0(RXD3/PCINT9)_63") (pintype "bidirectional"))
      (node (ref "IC5") (pin "1") (pinfunction "A_1") (pintype "input"))
    )
    (net (code "62") (name "/PJ1") (class "Default")
      (node (ref "IC2") (pin "64") (pinfunction "PJ1(TXD3/PCINT10)_64") (pintype "bidirectional"))
      (node (ref "IC5") (pin "2") (pinfunction "B_2") (pintype "input"))
    )
    (net (code "63") (name "/PJ2") (class "Default")
      (node (ref "IC2") (pin "65") (pinfunction "PJ2(XCK3/PCINT11)_65") (pintype "bidirectional"))
      (node (ref "IC5") (pin "3") (pinfunction "C_3") (pintype "input"))
    )
    (net (code "64") (name "/PJ3") (class "Default")
      (node (ref "IC2") (pin "66") (pinfunction "PJ3(PCINT12)_66") (pintype "bidirectional"))
      (node (ref "IC5") (pin "6") (pinfunction "G1_6") (pintype "input"))
    )
    (net (code "65") (name "/PJ4") (class "Default")
      (node (ref "IC2") (pin "67") (pinfunction "PJ4(PCINT13)_67") (pintype "bidirectional"))
      (node (ref "X3") (pin "2") (pinfunction "KL_2") (pintype "passive"))
    )
    (net (code "66") (name "/PJ5") (class "Default")
      (node (ref "IC2") (pin "68") (pinfunction "PJ5(PCINT14)_68") (pintype "bidirectional"))
      (node (ref "X3") (pin "8") (pinfunction "KL_8") (pintype "passive"))
    )
    (net (code "67") (name "/PJ6") (class "Default")
      (node (ref "IC2") (pin "69") (pinfunction "PJ6(PCINT15)_69") (pintype "bidirectional"))
      (node (ref "X3") (pin "10") (pinfunction "KL_10") (pintype "passive"))
    )
    (net (code "68") (name "/PL0") (class "Default")
      (node (ref "IC1") (pin "12") (pinfunction "O_12") (pintype "output"))
      (node (ref "IC2") (pin "35") (pinfunction "PL0(ICP4)_35") (pintype "bidirectional"))
    )
    (net (code "69") (name "/PL1") (class "Default")
      (node (ref "IC1") (pin "10") (pinfunction "O_10") (pintype "output"))
      (node (ref "IC2") (pin "36") (pinfunction "PL1(ICP5)_36") (pintype "bidirectional"))
    )
    (net (code "70") (name "/PL2") (class "Default")
      (node (ref "IC2") (pin "37") (pinfunction "PL2(T5)_37") (pintype "bidirectional"))
      (node (ref "X4") (pin "5") (pinfunction "KL_5") (pintype "passive"))
    )
    (net (code "71") (name "/PL3") (class "Default")
      (node (ref "IC2") (pin "38") (pinfunction "PL3(OC5A)_38") (pintype "bidirectional"))
      (node (ref "X4") (pin "6") (pinfunction "KL_6") (pintype "passive"))
    )
    (net (code "72") (name "/PL4") (class "Default")
      (node (ref "IC2") (pin "39") (pinfunction "PL4(OC5B)_39") (pintype "bidirectional"))
      (node (ref "X4") (pin "7") (pinfunction "KL_7") (pintype "passive"))
    )
    (net (code "73") (name "/PL5") (class "Default")
      (node (ref "IC2") (pin "40") (pinfunction "PL5(OC5C)_40") (pintype "bidirectional"))
      (node (ref "X4") (pin "8") (pinfunction "KL_8") (pintype "passive"))
    )
    (net (code "74") (name "/PL6") (class "Default")
      (node (ref "IC1") (pin "8") (pinfunction "O_8") (pintype "output"))
      (node (ref "IC2") (pin "41") (pinfunction "PL6_41") (pintype "bidirectional"))
    )
    (net (code "75") (name "/PL7") (class "Default")
      (node (ref "IC1") (pin "2") (pinfunction "O_2") (pintype "output"))
      (node (ref "IC2") (pin "42") (pinfunction "PL7_42") (pintype "bidirectional"))
    )
    (net (code "76") (name "/RESET") (class "Default")
      (node (ref "IC2") (pin "30") (pinfunction "RESET_30") (pintype "input"))
      (node (ref "JTAG") (pin "6") (pinfunction "6_6") (pintype "passive"))
      (node (ref "R37") (pin "1") (pinfunction "1_1") (pintype "passive"))
    )
    (net (code "77") (name "GND") (class "Default")
      (node (ref "+5V-POWER") (pin "C") (pinfunction "C_C") (pintype "passive"))
      (node (ref "C1") (pin "2") (pinfunction "2_2") (pintype "passive"))
      (node (ref "C10") (pin "2") (pinfunction "2_2") (pintype "passive"))
      (node (ref "C11") (pin "2") (pinfunction "2_2") (pintype "passive"))
      (node (ref "C12") (pin "2") (pinfunction "2_2") (pintype "passive"))
      (node (ref "C13") (pin "1") (pinfunction "1_1") (pintype "passive"))
      (node (ref "C14") (pin "-") (pinfunction "-_-") (pintype "passive"))
      (node (ref "C15") (pin "2") (pinfunction "2_2") (pintype "passive"))
      (node (ref "C16") (pin "2") (pinfunction "2_2") (pintype "passive"))
      (node (ref "C17") (pin "2") (pinfunction "2_2") (pintype "passive"))
      (node (ref "C18") (pin "2") (pinfunction "2_2") (pintype "passive"))
      (node (ref "C19") (pin "1") (pinfunction "1_1") (pintype "passive"))
      (node (ref "C2") (pin "2") (pinfunction "2_2") (pintype "passive"))
      (node (ref "C20") (pin "2") (pinfunction "2_2") (pintype "passive"))
      (node (ref "C21") (pin "2") (pinfunction "2_2") (pintype "passive"))
      (node (ref "C22") (pin "2") (pinfunction "2_2") (pintype "passive"))
      (node (ref "C23") (pin "2") (pinfunction "2_2") (pintype "passive"))
      (node (ref "C24") (pin "-") (pinfunction "-_-") (pintype "passive"))
      (node (ref "C25") (pin "-") (pinfunction "-_-") (pintype "passive"))
      (node (ref "C26") (pin "2") (pinfunction "2_2") (pintype "passive"))
      (node (ref "C3") (pin "1") (pinfunction "1_1") (pintype "passive"))
      (node (ref "C4") (pin "2") (pinfunction "2_2") (pintype "passive"))
      (node (ref "C5") (pin "2") (pinfunction "2_2") (pintype "passive"))
      (node (ref "C6") (pin "2") (pinfunction "2_2") (pintype "passive"))
      (node (ref "C7") (pin "2") (pinfunction "2_2") (pintype "passive"))
      (node (ref "C8") (pin "1") (pinfunction "1_1") (pintype "passive"))
      (node (ref "C9") (pin "2") (pinfunction "2_2") (pintype "passive"))
      (node (ref "IC1") (pin "5") (pinfunction "I_5") (pintype "input"))
      (node (ref "IC1") (pin "7") (pinfunction "GND_7") (pintype "power_in"))
      (node (ref "IC2") (pin "11") (pinfunction "GND_11") (pintype "power_in"))
      (node (ref "IC2") (pin "32") (pinfunction "GND1_32") (pintype "power_in"))
      (node (ref "IC2") (pin "62") (pinfunction "GND2_62") (pintype "power_in"))
      (node (ref "IC2") (pin "81") (pinfunction "GND3_81") (pintype "power_in"))
      (node (ref "IC2") (pin "99") (pinfunction "AGND_99") (pintype "power_in"))
      (node (ref "IC3") (pin "3") (pinfunction "GND_3") (pintype "power_in"))
      (node (ref "IC4") (pin "3") (pinfunction "GND_3") (pintype "power_in"))
      (node (ref "IC5") (pin "4") (pinfunction "G2A_4") (pintype "input"))
      (node (ref "IC5") (pin "5") (pinfunction "G2B_5") (pintype "input"))
      (node (ref "IC5") (pin "8") (pinfunction "GND_8") (pintype "power_in"))
      (node (ref "IC6") (pin "2") (pinfunction "GND_2") (pintype "power_in"))
      (node (ref "JP2") (pin "3") (pinfunction "3_3") (pintype "passive"))
      (node (ref "JP3") (pin "3") (pinfunction "3_3") (pintype "passive"))
      (node (ref "JTAG") (pin "10") (pinfunction "10_10") (pintype "passive"))
      (node (ref "JTAG") (pin "2") (pinfunction "2_2") (pintype "passive"))
      (node (ref "LCD1") (pin "1") (pinfunction "GND_1") (pintype "power_in"))
      (node (ref "LCD1") (pin "4") (pinfunction "RS(CS)_4") (pintype "input"))
      (node (ref "R1") (pin "1") (pinfunction "A_1") (pintype "passive"))
      (node (ref "R1") (pin "M1") (pinfunction "P$1_M1") (pintype "bidirectional"))
      (node (ref "R1") (pin "M2") (pinfunction "P$2_M2") (pintype "bidirectional"))
      (node (ref "R15") (pin "1") (pinfunction "1_1") (pintype "passive"))
      (node (ref "R16") (pin "1") (pinfunction "1_1") (pintype "passive"))
      (node (ref "R28") (pin "1") (pinfunction "1_1") (pintype "passive"))
      (node (ref "R6") (pin "1") (pinfunction "A_1") (pintype "passive"))
      (node (ref "R6") (pin "M1") (pinfunction "P$1_M1") (pintype "bidirectional"))
      (node (ref "R6") (pin "M2") (pinfunction "P$2_M2") (pintype "bidirectional"))
      (node (ref "S1") (pin "3") (pinfunction "3_3") (pintype "passive"))
      (node (ref "S1") (pin "4") (pinfunction "4_4") (pintype "passive"))
      (node (ref "S10") (pin "3") (pinfunction "O_3") (pintype "passive"))
      (node (ref "S11") (pin "3") (pinfunction "O_3") (pintype "passive"))
      (node (ref "S12") (pin "3") (pinfunction "O_3") (pintype "passive"))
      (node (ref "S2") (pin "3") (pinfunction "3_3") (pintype "passive"))
      (node (ref "S2") (pin "4") (pinfunction "4_4") (pintype "passive"))
      (node (ref "S3") (pin "1") (pinfunction "1_1") (pintype "passive"))
      (node (ref "S3") (pin "2") (pinfunction "2_2") (pintype "passive"))
      (node (ref "S4") (pin "1") (pinfunction "1_1") (pintype "passive"))
      (node (ref "S4") (pin "2") (pinfunction "2_2") (pintype "passive"))
      (node (ref "S5") (pin "3") (pinfunction "O_3") (pintype "passive"))
      (node (ref "S6") (pin "3") (pinfunction "O_3") (pintype "passive"))
      (node (ref "S7") (pin "3") (pinfunction "O_3") (pintype "passive"))
      (node (ref "S8") (pin "3") (pinfunction "O_3") (pintype "passive"))
      (node (ref "S9") (pin "3") (pinfunction "O_3") (pintype "passive"))
      (node (ref "U$1") (pin "1") (pinfunction "1_1") (pintype "bidirectional"))
      (node (ref "U$1") (pin "10") (pinfunction "L/R+_10") (pintype "bidirectional"))
      (node (ref "U$1") (pin "11") (pinfunction "CASE_11") (pintype "bidirectional"))
      (node (ref "U$1") (pin "12") (pinfunction "CASE_12") (pintype "bidirectional"))
      (node (ref "U$1") (pin "15") (pinfunction "CASE_15") (pintype "bidirectional"))
      (node (ref "U$1") (pin "16") (pinfunction "CASE_16") (pintype "bidirectional"))
      (node (ref "U$1") (pin "3") (pinfunction "3_3") (pintype "bidirectional"))
      (node (ref "U$1") (pin "7") (pinfunction "U/D-_7") (pintype "bidirectional"))
      (node (ref "U$2") (pin "1") (pinfunction "GND1_1") (pintype "bidirectional"))
      (node (ref "U$2") (pin "6") (pinfunction "GND2_6") (pintype "bidirectional"))
      (node (ref "U1") (pin "3") (pinfunction "GND_3") (pintype "passive"))
      (node (ref "V1") (pin "2") (pinfunction "S_2") (pintype "passive"))
      (node (ref "V10") (pin "2") (pinfunction "S_2") (pintype "passive"))
      (node (ref "V11") (pin "2") (pinfunction "S_2") (pintype "passive"))
      (node (ref "V12") (pin "2") (pinfunction "S_2") (pintype "passive"))
      (node (ref "V13") (pin "2") (pinfunction "S_2") (pintype "passive"))
      (node (ref "V14") (pin "2") (pinfunction "S_2") (pintype "passive"))
      (node (ref "V15") (pin "2") (pinfunction "S_2") (pintype "passive"))
      (node (ref "V16") (pin "2") (pinfunction "S_2") (pintype "passive"))
      (node (ref "V17") (pin "2") (pinfunction "S_2") (pintype "passive"))
      (node (ref "V18") (pin "2") (pinfunction "S_2") (pintype "passive"))
      (node (ref "V19") (pin "2") (pinfunction "S_2") (pintype "passive"))
      (node (ref "V2") (pin "2") (pinfunction "S_2") (pintype "passive"))
      (node (ref "V20") (pin "2") (pinfunction "S_2") (pintype "passive"))
      (node (ref "V3") (pin "2") (pinfunction "S_2") (pintype "passive"))
      (node (ref "V4") (pin "2") (pinfunction "S_2") (pintype "passive"))
      (node (ref "V5") (pin "2") (pinfunction "S_2") (pintype "passive"))
      (node (ref "V6") (pin "2") (pinfunction "S_2") (pintype "passive"))
      (node (ref "V7") (pin "2") (pinfunction "S_2") (pintype "passive"))
      (node (ref "V8") (pin "2") (pinfunction "S_2") (pintype "passive"))
      (node (ref "V9") (pin "2") (pinfunction "S_2") (pintype "passive"))
      (node (ref "X1") (pin "10") (pinfunction "KL_10") (pintype "passive"))
      (node (ref "X2") (pin "1.1") (pinfunction "KL_1.1") (pintype "passive"))
      (node (ref "X2") (pin "1.2") (pinfunction "KL_1.2") (pintype "passive"))
      (node (ref "X3") (pin "12") (pinfunction "KL_12") (pintype "passive"))
      (node (ref "X3") (pin "6") (pinfunction "KL_6") (pintype "passive"))
      (node (ref "X4") (pin "10") (pinfunction "KL_10") (pintype "passive"))
      (node (ref "X5") (pin "10") (pinfunction "KL_10") (pintype "passive"))
    )
    (net (code "78") (name "Net-(+5V-POWER-PadA)") (class "Default")
      (node (ref "+5V-POWER") (pin "A") (pinfunction "A_A") (pintype "passive"))
      (node (ref "R11") (pin "2") (pinfunction "2_2") (pintype "passive"))
    )
    (net (code "79") (name "Net-(F1-Pad1)") (class "Default")
      (node (ref "F1") (pin "1") (pinfunction "1_1") (pintype "passive"))
      (node (ref "X2") (pin "2.1") (pinfunction "KL_2.1") (pintype "passive"))
      (node (ref "X2") (pin "2.2") (pinfunction "KL_2.2") (pintype "passive"))
    )
    (net (code "80") (name "Net-(F1-Pad2)") (class "Default")
      (node (ref "F1") (pin "2") (pinfunction "2_2") (pintype "passive"))
      (node (ref "JP1") (pin "1") (pinfunction "1_1") (pintype "passive"))
    )
    (net (code "81") (name "Net-(F2-Pad2)") (class "Default")
      (node (ref "F2") (pin "2") (pinfunction "2_2") (pintype "passive"))
      (node (ref "JP1") (pin "3") (pinfunction "3_3") (pintype "passive"))
    )
    (net (code "82") (name "Net-(H0-PadC)") (class "Default")
      (node (ref "H0") (pin "C") (pinfunction "C_C") (pintype "passive"))
      (node (ref "R36") (pin "2") (pinfunction "2_2") (pintype "passive"))
    )
    (net (code "83") (name "Net-(H1-PadC)") (class "Default")
      (node (ref "H1") (pin "C") (pinfunction "C_C") (pintype "passive"))
      (node (ref "R35") (pin "2") (pinfunction "2_2") (pintype "passive"))
    )
    (net (code "84") (name "Net-(H2-PadC)") (class "Default")
      (node (ref "H2") (pin "C") (pinfunction "C_C") (pintype "passive"))
      (node (ref "R34") (pin "2") (pinfunction "2_2") (pintype "passive"))
    )
    (net (code "85") (name "Net-(H3-PadC)") (class "Default")
      (node (ref "H3") (pin "C") (pinfunction "C_C") (pintype "passive"))
      (node (ref "R33") (pin "2") (pinfunction "2_2") (pintype "passive"))
    )
    (net (code "86") (name "Net-(H4-PadC)") (class "Default")
      (node (ref "H4") (pin "C") (pinfunction "C_C") (pintype "passive"))
      (node (ref "R32") (pin "2") (pinfunction "2_2") (pintype "passive"))
    )
    (net (code "87") (name "Net-(H5-PadC)") (class "Default")
      (node (ref "H5") (pin "C") (pinfunction "C_C") (pintype "passive"))
      (node (ref "R31") (pin "2") (pinfunction "2_2") (pintype "passive"))
    )
    (net (code "88") (name "Net-(H6-PadC)") (class "Default")
      (node (ref "H6") (pin "C") (pinfunction "C_C") (pintype "passive"))
      (node (ref "R30") (pin "2") (pinfunction "2_2") (pintype "passive"))
    )
    (net (code "89") (name "Net-(H7-PadC)") (class "Default")
      (node (ref "H7") (pin "C") (pinfunction "C_C") (pintype "passive"))
      (node (ref "R29") (pin "2") (pinfunction "2_2") (pintype "passive"))
    )
    (net (code "90") (name "Net-(H8-PadC)") (class "Default")
      (node (ref "H8") (pin "C") (pinfunction "C_C") (pintype "passive"))
      (node (ref "R24") (pin "2") (pinfunction "2_2") (pintype "passive"))
    )
    (net (code "91") (name "Net-(H9-PadC)") (class "Default")
      (node (ref "H9") (pin "C") (pinfunction "C_C") (pintype "passive"))
      (node (ref "R25") (pin "2") (pinfunction "2_2") (pintype "passive"))
    )
    (net (code "92") (name "Net-(H10-PadC)") (class "Default")
      (node (ref "H10") (pin "C") (pinfunction "C_C") (pintype "passive"))
      (node (ref "R22") (pin "2") (pinfunction "2_2") (pintype "passive"))
    )
    (net (code "93") (name "Net-(H11-PadC)") (class "Default")
      (node (ref "H11") (pin "C") (pinfunction "C_C") (pintype "passive"))
      (node (ref "R23") (pin "2") (pinfunction "2_2") (pintype "passive"))
    )
    (net (code "94") (name "Net-(H12-PadC)") (class "Default")
      (node (ref "H12") (pin "C") (pinfunction "C_C") (pintype "passive"))
      (node (ref "R20") (pin "2") (pinfunction "2_2") (pintype "passive"))
    )
    (net (code "95") (name "Net-(H13-PadC)") (class "Default")
      (node (ref "H13") (pin "C") (pinfunction "C_C") (pintype "passive"))
      (node (ref "R21") (pin "2") (pinfunction "2_2") (pintype "passive"))
    )
    (net (code "96") (name "Net-(H14-PadC)") (class "Default")
      (node (ref "H14") (pin "C") (pinfunction "C_C") (pintype "passive"))
      (node (ref "R18") (pin "2") (pinfunction "2_2") (pintype "passive"))
    )
    (net (code "97") (name "Net-(H15-PadC)") (class "Default")
      (node (ref "H15") (pin "C") (pinfunction "C_C") (pintype "passive"))
      (node (ref "R19") (pin "2") (pinfunction "2_2") (pintype "passive"))
    )
    (net (code "98") (name "Net-(IC1A-I)") (class "Default")
      (node (ref "C1") (pin "1") (pinfunction "1_1") (pintype "passive"))
      (node (ref "IC1") (pin "13") (pinfunction "I_13") (pintype "input"))
      (node (ref "R3") (pin "2") (pinfunction "2_2") (pintype "passive"))
      (node (ref "S1") (pin "1") (pinfunction "1_1") (pintype "passive"))
      (node (ref "S1") (pin "2") (pinfunction "2_2") (pintype "passive"))
    )
    (net (code "99") (name "Net-(IC1B-I)") (class "Default")
      (node (ref "C2") (pin "1") (pinfunction "1_1") (pintype "passive"))
      (node (ref "IC1") (pin "11") (pinfunction "I_11") (pintype "input"))
      (node (ref "R4") (pin "2") (pinfunction "2_2") (pintype "passive"))
      (node (ref "S2") (pin "1") (pinfunction "1_1") (pintype "passive"))
      (node (ref "S2") (pin "2") (pinfunction "2_2") (pintype "passive"))
    )
    (net (code "100") (name "Net-(IC1C-I)") (class "Default")
      (node (ref "C10") (pin "1") (pinfunction "1_1") (pintype "passive"))
      (node (ref "IC1") (pin "9") (pinfunction "I_9") (pintype "input"))
      (node (ref "R8") (pin "2") (pinfunction "2_2") (pintype "passive"))
      (node (ref "S3") (pin "3") (pinfunction "3_3") (pintype "passive"))
      (node (ref "S3") (pin "4") (pinfunction "4_4") (pintype "passive"))
    )
    (net (code "101") (name "Net-(IC1D-I)") (class "Default")
      (node (ref "C11") (pin "1") (pinfunction "1_1") (pintype "passive"))
      (node (ref "IC1") (pin "1") (pinfunction "I_1") (pintype "input"))
      (node (ref "R9") (pin "2") (pinfunction "2_2") (pintype "passive"))
      (node (ref "S4") (pin "3") (pinfunction "3_3") (pintype "passive"))
      (node (ref "S4") (pin "4") (pinfunction "4_4") (pintype "passive"))
    )
    (net (code "102") (name "Net-(IC1E-I)") (class "Default")
      (node (ref "C23") (pin "1") (pinfunction "1_1") (pintype "passive"))
      (node (ref "IC1") (pin "3") (pinfunction "I_3") (pintype "input"))
      (node (ref "R45") (pin "2") (pinfunction "2_2") (pintype "passive"))
      (node (ref "U$1") (pin "2") (pinfunction "2_2") (pintype "bidirectional"))
      (node (ref "U$1") (pin "4") (pinfunction "4_4") (pintype "bidirectional"))
    )
    (net (code "103") (name "Net-(IC2-(ALE)PG2)") (class "Default")
      (node (ref "C18") (pin "1") (pinfunction "1_1") (pintype "passive"))
      (node (ref "IC2") (pin "70") (pinfunction "(ALE)PG2_70") (pintype "bidirectional"))
      (node (ref "Q2") (pin "2") (pinfunction "2_2") (pintype "passive"))
    )
    (net (code "104") (name "Net-(IC2-(OC3C{slash}INT5)PE5)") (class "Default")
      (node (ref "IC2") (pin "7") (pinfunction "(OC3C/INT5)PE5_7") (pintype "bidirectional"))
      (node (ref "LSP3") (pin "MP") (pinfunction "MP_MP") (pintype "passive"))
    )
    (net (code "105") (name "Net-(IC2-(TOSC1)PG4)") (class "Default")
      (node (ref "C17") (pin "1") (pinfunction "1_1") (pintype "passive"))
      (node (ref "IC2") (pin "29") (pinfunction "(TOSC1)PG4_29") (pintype "bidirectional"))
      (node (ref "Q2") (pin "1") (pinfunction "1_1") (pintype "passive"))
    )
    (net (code "106") (name "Net-(IC2-AREF)") (class "Default")
      (node (ref "C13") (pin "2") (pinfunction "2_2") (pintype "passive"))
      (node (ref "IC2") (pin "98") (pinfunction "AREF_98") (pintype "bidirectional"))
    )
    (net (code "107") (name "Net-(IC2-AVCC)") (class "Default")
      (node (ref "C3") (pin "2") (pinfunction "2_2") (pintype "passive"))
      (node (ref "IC2") (pin "100") (pinfunction "AVCC_100") (pintype "power_in"))
      (node (ref "L1") (pin "2") (pinfunction "2_2") (pintype "passive"))
    )
    (net (code "108") (name "Net-(IC2-XTAL1)") (class "Default")
      (node (ref "C9") (pin "1") (pinfunction "1_1") (pintype "passive"))
      (node (ref "IC2") (pin "34") (pinfunction "XTAL1_34") (pintype "input"))
      (node (ref "Q1") (pin "1") (pinfunction "1_1") (pintype "passive"))
    )
    (net (code "109") (name "Net-(IC2-XTAL2)") (class "Default")
      (node (ref "C8") (pin "2") (pinfunction "2_2") (pintype "passive"))
      (node (ref "IC2") (pin "33") (pinfunction "XTAL2_33") (pintype "output"))
      (node (ref "Q1") (pin "2") (pinfunction "2_2") (pintype "passive"))
    )
    (net (code "110") (name "Net-(IC5A-Y0)") (class "Default")
      (node (ref "IC5") (pin "15") (pinfunction "Y0_15") (pintype "output"))
      (node (ref "Q10") (pin "1") (pinfunction "G_1") (pintype "passive"))
    )
    (net (code "111") (name "Net-(IC5A-Y1)") (class "Default")
      (node (ref "IC5") (pin "14") (pinfunction "Y1_14") (pintype "output"))
      (node (ref "Q9") (pin "1") (pinfunction "G_1") (pintype "passive"))
    )
    (net (code "112") (name "Net-(IC5A-Y2)") (class "Default")
      (node (ref "IC5") (pin "13") (pinfunction "Y2_13") (pintype "output"))
      (node (ref "Q8") (pin "1") (pinfunction "G_1") (pintype "passive"))
    )
    (net (code "113") (name "Net-(IC5A-Y3)") (class "Default")
      (node (ref "IC5") (pin "12") (pinfunction "Y3_12") (pintype "output"))
      (node (ref "Q7") (pin "1") (pinfunction "G_1") (pintype "passive"))
    )
    (net (code "114") (name "Net-(IC5A-Y4)") (class "Default")
      (node (ref "IC5") (pin "11") (pinfunction "Y4_11") (pintype "output"))
      (node (ref "Q6") (pin "1") (pinfunction "G_1") (pintype "passive"))
    )
    (net (code "115") (name "Net-(IC5A-Y5)") (class "Default")
      (node (ref "IC5") (pin "10") (pinfunction "Y5_10") (pintype "output"))
      (node (ref "Q5") (pin "1") (pinfunction "G_1") (pintype "passive"))
    )
    (net (code "116") (name "Net-(IC5A-Y6)") (class "Default")
      (node (ref "IC5") (pin "9") (pinfunction "Y6_9") (pintype "output"))
      (node (ref "Q4") (pin "1") (pinfunction "G_1") (pintype "passive"))
    )
    (net (code "117") (name "Net-(IC5A-Y7)") (class "Default")
      (node (ref "IC5") (pin "7") (pinfunction "Y7_7") (pintype "output"))
      (node (ref "Q3") (pin "1") (pinfunction "G_1") (pintype "passive"))
    )
    (net (code "118") (name "Net-(IC6-NC{slash}FB)") (class "Default")
      (node (ref "C21") (pin "1") (pinfunction "1_1") (pintype "passive"))
      (node (ref "IC6") (pin "4") (pinfunction "NC/FB_4") (pintype "passive"))
    )
    (net (code "119") (name "Net-(LCD1-CONTR)") (class "Default")
      (node (ref "LCD1") (pin "3") (pinfunction "CONTR_3") (pintype "input"))
      (node (ref "R13") (pin "1") (pinfunction "A_1") (pintype "passive"))
    )
    (net (code "120") (name "Net-(LCD1-E(SCLK))") (class "Default")
      (node (ref "LCD1") (pin "6") (pinfunction "E(SCLK)_6") (pintype "input"))
      (node (ref "R12") (pin "1") (pinfunction "1_1") (pintype "passive"))
      (node (ref "R15") (pin "2") (pinfunction "2_2") (pintype "passive"))
    )
    (net (code "121") (name "Net-(LCD1-LED+)") (class "Default")
      (node (ref "LCD1") (pin "17") (pinfunction "LED+_17") (pintype "passive"))
      (node (ref "R17") (pin "1") (pinfunction "1_1") (pintype "passive"))
    )
    (net (code "122") (name "Net-(LCD1-LED-)") (class "Default")
      (node (ref "LCD1") (pin "18") (pinfunction "LED-_18") (pintype "passive"))
      (node (ref "V4") (pin "3") (pinfunction "D_3") (pintype "passive"))
    )
    (net (code "123") (name "Net-(LCD1-R{slash}W(SID))") (class "Default")
      (node (ref "LCD1") (pin "5") (pinfunction "R/W(SID)_5") (pintype "input"))
      (node (ref "R14") (pin "1") (pinfunction "1_1") (pintype "passive"))
      (node (ref "R16") (pin "2") (pinfunction "2_2") (pintype "passive"))
    )
    (net (code "124") (name "Net-(Q3-D)") (class "Default")
      (node (ref "Q3") (pin "3") (pinfunction "D_3") (pintype "passive"))
      (node (ref "X3") (pin "4") (pinfunction "KL_4") (pintype "passive"))
    )
    (net (code "125") (name "Net-(Q4-D)") (class "Default")
      (node (ref "Q4") (pin "3") (pinfunction "D_3") (pintype "passive"))
      (node (ref "X3") (pin "13") (pinfunction "KL_13") (pintype "passive"))
    )
    (net (code "126") (name "Net-(Q5-D)") (class "Default")
      (node (ref "Q5") (pin "3") (pinfunction "D_3") (pintype "passive"))
      (node (ref "X3") (pin "11") (pinfunction "KL_11") (pintype "passive"))
    )
    (net (code "127") (name "Net-(Q6-D)") (class "Default")
      (node (ref "Q6") (pin "3") (pinfunction "D_3") (pintype "passive"))
      (node (ref "X3") (pin "9") (pinfunction "KL_9") (pintype "passive"))
    )
    (net (code "128") (name "Net-(Q7-D)") (class "Default")
      (node (ref "Q7") (pin "3") (pinfunction "D_3") (pintype "passive"))
      (node (ref "X3") (pin "7") (pinfunction "KL_7") (pintype "passive"))
    )
    (net (code "129") (name "Net-(Q8-D)") (class "Default")
      (node (ref "Q8") (pin "3") (pinfunction "D_3") (pintype "passive"))
      (node (ref "X3") (pin "5") (pinfunction "KL_5") (pintype "passive"))
    )
    (net (code "130") (name "Net-(Q9-D)") (class "Default")
      (node (ref "Q9") (pin "3") (pinfunction "D_3") (pintype "passive"))
      (node (ref "X3") (pin "3") (pinfunction "KL_3") (pintype "passive"))
    )
    (net (code "131") (name "Net-(Q10-D)") (class "Default")
      (node (ref "Q10") (pin "3") (pinfunction "D_3") (pintype "passive"))
      (node (ref "X3") (pin "1") (pinfunction "KL_1") (pintype "passive"))
    )
    (net (code "132") (name "Net-(R27-A)") (class "Default")
      (node (ref "R26") (pin "1") (pinfunction "1_1") (pintype "passive"))
      (node (ref "R27") (pin "1") (pinfunction "A_1") (pintype "passive"))
      (node (ref "U$3") (pin "E") (pinfunction "E_E") (pintype "passive"))
    )
    (net (code "133") (name "Net-(R27-E)") (class "Default")
      (node (ref "R27") (pin "2") (pinfunction "S_2") (pintype "passive"))
      (node (ref "R27") (pin "3") (pinfunction "E_3") (pintype "passive"))
      (node (ref "R28") (pin "2") (pinfunction "2_2") (pintype "passive"))
    )
    (net (code "134") (name "Net-(RGB1A-C)") (class "Default")
      (node (ref "R7") (pin "2") (pinfunction "2_2") (pintype "passive"))
      (node (ref "RGB1") (pin "1") (pinfunction "C_1") (pintype "passive"))
    )
    (net (code "135") (name "Net-(RGB1B-C)") (class "Default")
      (node (ref "R5") (pin "2") (pinfunction "2_2") (pintype "passive"))
      (node (ref "RGB1") (pin "2") (pinfunction "C_2") (pintype "passive"))
    )
    (net (code "136") (name "Net-(RGB1C-C)") (class "Default")
      (node (ref "R2") (pin "2") (pinfunction "2_2") (pintype "passive"))
      (node (ref "RGB1") (pin "3") (pinfunction "C_3") (pintype "passive"))
    )
    (net (code "137") (name "Net-(U$2-CC1)") (class "Default")
      (node (ref "CC1") (pin "MP") (pinfunction "MP_MP") (pintype "passive"))
      (node (ref "U$2") (pin "3") (pinfunction "CC1_3") (pintype "bidirectional"))
    )
    (net (code "138") (name "Net-(U$2-CC2)") (class "Default")
      (node (ref "CC2") (pin "MP") (pinfunction "MP_MP") (pintype "passive"))
      (node (ref "U$2") (pin "4") (pinfunction "CC2_4") (pintype "bidirectional"))
    )
    (net (code "139") (name "Net-(U$2-VBUS1)") (class "Default")
      (node (ref "F2") (pin "1") (pinfunction "1_1") (pintype "passive"))
      (node (ref "U$2") (pin "2") (pinfunction "VBUS1_2") (pintype "bidirectional"))
      (node (ref "U$2") (pin "5") (pinfunction "VBUS2_5") (pintype "bidirectional"))
    )
    (net (code "140") (name "Net-(V1-D)") (class "Default")
      (node (ref "R2") (pin "1") (pinfunction "1_1") (pintype "passive"))
      (node (ref "V1") (pin "3") (pinfunction "D_3") (pintype "passive"))
    )
    (net (code "141") (name "Net-(V2-D)") (class "Default")
      (node (ref "R5") (pin "1") (pinfunction "1_1") (pintype "passive"))
      (node (ref "V2") (pin "3") (pinfunction "D_3") (pintype "passive"))
    )
    (net (code "142") (name "Net-(V3-D)") (class "Default")
      (node (ref "R7") (pin "1") (pinfunction "1_1") (pintype "passive"))
      (node (ref "V3") (pin "3") (pinfunction "D_3") (pintype "passive"))
    )
    (net (code "143") (name "Net-(V5-D)") (class "Default")
      (node (ref "R36") (pin "1") (pinfunction "1_1") (pintype "passive"))
      (node (ref "V5") (pin "3") (pinfunction "D_3") (pintype "passive"))
    )
    (net (code "144") (name "Net-(V6-D)") (class "Default")
      (node (ref "R35") (pin "1") (pinfunction "1_1") (pintype "passive"))
      (node (ref "V6") (pin "3") (pinfunction "D_3") (pintype "passive"))
    )
    (net (code "145") (name "Net-(V7-D)") (class "Default")
      (node (ref "R34") (pin "1") (pinfunction "1_1") (pintype "passive"))
      (node (ref "V7") (pin "3") (pinfunction "D_3") (pintype "passive"))
    )
    (net (code "146") (name "Net-(V8-D)") (class "Default")
      (node (ref "R33") (pin "1") (pinfunction "1_1") (pintype "passive"))
      (node (ref "V8") (pin "3") (pinfunction "D_3") (pintype "passive"))
    )
    (net (code "147") (name "Net-(V9-D)") (class "Default")
      (node (ref "R32") (pin "1") (pinfunction "1_1") (pintype "passive"))
      (node (ref "V9") (pin "3") (pinfunction "D_3") (pintype "passive"))
    )
    (net (code "148") (name "Net-(V10-D)") (class "Default")
      (node (ref "R31") (pin "1") (pinfunction "1_1") (pintype "passive"))
      (node (ref "V10") (pin "3") (pinfunction "D_3") (pintype "passive"))
    )
    (net (code "149") (name "Net-(V11-D)") (class "Default")
      (node (ref "R30") (pin "1") (pinfunction "1_1") (pintype "passive"))
      (node (ref "V11") (pin "3") (pinfunction "D_3") (pintype "passive"))
    )
    (net (code "150") (name "Net-(V12-D)") (class "Default")
      (node (ref "R29") (pin "1") (pinfunction "1_1") (pintype "passive"))
      (node (ref "V12") (pin "3") (pinfunction "D_3") (pintype "passive"))
    )
    (net (code "151") (name "Net-(V13-D)") (class "Default")
      (node (ref "R24") (pin "1") (pinfunction "1_1") (pintype "passive"))
      (node (ref "V13") (pin "3") (pinfunction "D_3") (pintype "passive"))
    )
    (net (code "152") (name "Net-(V14-D)") (class "Default")
      (node (ref "R25") (pin "1") (pinfunction "1_1") (pintype "passive"))
      (node (ref "V14") (pin "3") (pinfunction "D_3") (pintype "passive"))
    )
    (net (code "153") (name "Net-(V15-D)") (class "Default")
      (node (ref "R22") (pin "1") (pinfunction "1_1") (pintype "passive"))
      (node (ref "V15") (pin "3") (pinfunction "D_3") (pintype "passive"))
    )
    (net (code "154") (name "Net-(V16-D)") (class "Default")
      (node (ref "R23") (pin "1") (pinfunction "1_1") (pintype "passive"))
      (node (ref "V16") (pin "3") (pinfunction "D_3") (pintype "passive"))
    )
    (net (code "155") (name "Net-(V17-D)") (class "Default")
      (node (ref "R20") (pin "1") (pinfunction "1_1") (pintype "passive"))
      (node (ref "V17") (pin "3") (pinfunction "D_3") (pintype "passive"))
    )
    (net (code "156") (name "Net-(V18-D)") (class "Default")
      (node (ref "R21") (pin "1") (pinfunction "1_1") (pintype "passive"))
      (node (ref "V18") (pin "3") (pinfunction "D_3") (pintype "passive"))
    )
    (net (code "157") (name "Net-(V19-D)") (class "Default")
      (node (ref "R18") (pin "1") (pinfunction "1_1") (pintype "passive"))
      (node (ref "V19") (pin "3") (pinfunction "D_3") (pintype "passive"))
    )
    (net (code "158") (name "Net-(V20-D)") (class "Default")
      (node (ref "R19") (pin "1") (pinfunction "1_1") (pintype "passive"))
      (node (ref "V20") (pin "3") (pinfunction "D_3") (pintype "passive"))
    )
    (net (code "159") (name "VCC") (class "Default")
      (node (ref "C12") (pin "1") (pinfunction "1_1") (pintype "passive"))
      (node (ref "C14") (pin "+") (pinfunction "+_+") (pintype "passive"))
      (node (ref "C16") (pin "1") (pinfunction "1_1") (pintype "passive"))
      (node (ref "C20") (pin "1") (pinfunction "1_1") (pintype "passive"))
      (node (ref "C24") (pin "+") (pinfunction "+_+") (pintype "passive"))
      (node (ref "C25") (pin "+") (pinfunction "+_+") (pintype "passive"))
      (node (ref "C26") (pin "1") (pinfunction "1_1") (pintype "passive"))
      (node (ref "C4") (pin "1") (pinfunction "1_1") (pintype "passive"))
      (node (ref "C5") (pin "1") (pinfunction "1_1") (pintype "passive"))
      (node (ref "C6") (pin "1") (pinfunction "1_1") (pintype "passive"))
      (node (ref "C7") (pin "1") (pinfunction "1_1") (pintype "passive"))
      (node (ref "H0") (pin "A") (pinfunction "A_A") (pintype "passive"))
      (node (ref "H1") (pin "A") (pinfunction "A_A") (pintype "passive"))
      (node (ref "H10") (pin "A") (pinfunction "A_A") (pintype "passive"))
      (node (ref "H11") (pin "A") (pinfunction "A_A") (pintype "passive"))
      (node (ref "H12") (pin "A") (pinfunction "A_A") (pintype "passive"))
      (node (ref "H13") (pin "A") (pinfunction "A_A") (pintype "passive"))
      (node (ref "H14") (pin "A") (pinfunction "A_A") (pintype "passive"))
      (node (ref "H15") (pin "A") (pinfunction "A_A") (pintype "passive"))
      (node (ref "H2") (pin "A") (pinfunction "A_A") (pintype "passive"))
      (node (ref "H3") (pin "A") (pinfunction "A_A") (pintype "passive"))
      (node (ref "H4") (pin "A") (pinfunction "A_A") (pintype "passive"))
      (node (ref "H5") (pin "A") (pinfunction "A_A") (pintype "passive"))
      (node (ref "H6") (pin "A") (pinfunction "A_A") (pintype "passive"))
      (node (ref "H7") (pin "A") (pinfunction "A_A") (pintype "passive"))
      (node (ref "H8") (pin "A") (pinfunction "A_A") (pintype "passive"))
      (node (ref "H9") (pin "A") (pinfunction "A_A") (pintype "passive"))
      (node (ref "IC1") (pin "14") (pinfunction "VCC_14") (pintype "power_in"))
      (node (ref "IC2") (pin "10") (pinfunction "VCC_10") (pintype "power_in"))
      (node (ref "IC2") (pin "31") (pinfunction "VCC1_31") (pintype "power_in"))
      (node (ref "IC2") (pin "61") (pinfunction "VCC2_61") (pintype "power_in"))
      (node (ref "IC2") (pin "80") (pinfunction "VCC3_80") (pintype "power_in"))
      (node (ref "IC3") (pin "1") (pinfunction "VCC_1") (pintype "power_in"))
      (node (ref "IC4") (pin "1") (pinfunction "VCC_1") (pintype "power_in"))
      (node (ref "IC5") (pin "16") (pinfunction "VCC_16") (pintype "power_in"))
      (node (ref "IC6") (pin "1") (pinfunction "IN_1") (pintype "input"))
      (node (ref "IC6") (pin "3") (pinfunction "ON/~{OFF}_3") (pintype "input"))
      (node (ref "JP1") (pin "2") (pinfunction "2_2") (pintype "passive"))
      (node (ref "JP2") (pin "2") (pinfunction "2_2") (pintype "passive"))
      (node (ref "JP3") (pin "2") (pinfunction "2_2") (pintype "passive"))
      (node (ref "JTAG") (pin "4") (pinfunction "4_4") (pintype "passive"))
      (node (ref "L1") (pin "1") (pinfunction "1_1") (pintype "passive"))
      (node (ref "Q10") (pin "2") (pinfunction "S_2") (pintype "passive"))
      (node (ref "Q3") (pin "2") (pinfunction "S_2") (pintype "passive"))
      (node (ref "Q4") (pin "2") (pinfunction "S_2") (pintype "passive"))
      (node (ref "Q5") (pin "2") (pinfunction "S_2") (pintype "passive"))
      (node (ref "Q6") (pin "2") (pinfunction "S_2") (pintype "passive"))
      (node (ref "Q7") (pin "2") (pinfunction "S_2") (pintype "passive"))
      (node (ref "Q8") (pin "2") (pinfunction "S_2") (pintype "passive"))
      (node (ref "Q9") (pin "2") (pinfunction "S_2") (pintype "passive"))
      (node (ref "R1") (pin "3") (pinfunction "E_3") (pintype "passive"))
      (node (ref "R11") (pin "1") (pinfunction "1_1") (pintype "passive"))
      (node (ref "R17") (pin "2") (pinfunction "2_2") (pintype "passive"))
      (node (ref "R3") (pin "1") (pinfunction "1_1") (pintype "passive"))
      (node (ref "R37") (pin "2") (pinfunction "2_2") (pintype "passive"))
      (node (ref "R4") (pin "1") (pinfunction "1_1") (pintype "passive"))
      (node (ref "R45") (pin "1") (pinfunction "1_1") (pintype "passive"))
      (node (ref "R6") (pin "3") (pinfunction "E_3") (pintype "passive"))
      (node (ref "R8") (pin "1") (pinfunction "1_1") (pintype "passive"))
      (node (ref "R9") (pin "1") (pinfunction "1_1") (pintype "passive"))
      (node (ref "RGB1") (pin "4") (pinfunction "A_4") (pintype "passive"))
      (node (ref "RGB1") (pin "5") (pinfunction "A_5") (pintype "passive"))
      (node (ref "RGB1") (pin "6") (pinfunction "A_6") (pintype "passive"))
      (node (ref "S10") (pin "1") (pinfunction "S_1") (pintype "passive"))
      (node (ref "S11") (pin "1") (pinfunction "S_1") (pintype "passive"))
      (node (ref "S12") (pin "1") (pinfunction "S_1") (pintype "passive"))
      (node (ref "S5") (pin "1") (pinfunction "S_1") (pintype "passive"))
      (node (ref "S6") (pin "1") (pinfunction "S_1") (pintype "passive"))
      (node (ref "S7") (pin "1") (pinfunction "S_1") (pintype "passive"))
      (node (ref "S8") (pin "1") (pinfunction "S_1") (pintype "passive"))
      (node (ref "S9") (pin "1") (pinfunction "S_1") (pintype "passive"))
      (node (ref "U$1") (pin "5") (pinfunction "U/D+_5") (pintype "bidirectional"))
      (node (ref "U$1") (pin "8") (pinfunction "L/R-_8") (pintype "bidirectional"))
      (node (ref "U$3") (pin "C") (pinfunction "C_C") (pintype "passive"))
      (node (ref "U1") (pin "1") (pinfunction "+VS_1") (pintype "passive"))
      (node (ref "X1") (pin "9") (pinfunction "KL_9") (pintype "passive"))
      (node (ref "X3") (pin "14") (pinfunction "KL_14") (pintype "passive"))
      (node (ref "X4") (pin "9") (pinfunction "KL_9") (pintype "passive"))
      (node (ref "X5") (pin "9") (pinfunction "KL_9") (pintype "passive"))
    )
    (net (code "160") (name "unconnected-(IC1F-O-Pad6)") (class "Default")
      (node (ref "IC1") (pin "6") (pinfunction "O_6") (pintype "output"))
    )
    (net (code "161") (name "unconnected-(IC2-(CLKO{slash}ICP3{slash}INT7)PE7-Pad9)") (class "Default")
      (node (ref "IC2") (pin "9") (pinfunction "(CLKO/ICP3/INT7)PE7_9") (pintype "bidirectional"))
    )
    (net (code "162") (name "unconnected-(IC2-(T3{slash}INT6)PE6-Pad8)") (class "Default")
      (node (ref "IC2") (pin "8") (pinfunction "(T3/INT6)PE6_8") (pintype "bidirectional"))
    )
    (net (code "163") (name "unconnected-(IC2-(TOSC2)PG3-Pad28)") (class "Default")
      (node (ref "IC2") (pin "28") (pinfunction "(TOSC2)PG3_28") (pintype "bidirectional"))
    )
    (net (code "164") (name "unconnected-(IC2-PH0(RXD2)-Pad12)") (class "Default")
      (node (ref "IC2") (pin "12") (pinfunction "PH0(RXD2)_12") (pintype "bidirectional"))
    )
    (net (code "165") (name "unconnected-(IC2-PH1(TXD2)-Pad13)") (class "Default")
      (node (ref "IC2") (pin "13") (pinfunction "PH1(TXD2)_13") (pintype "bidirectional"))
    )
    (net (code "166") (name "unconnected-(IC2-PH2(XCK2)-Pad14)") (class "Default")
      (node (ref "IC2") (pin "14") (pinfunction "PH2(XCK2)_14") (pintype "bidirectional"))
    )
    (net (code "167") (name "unconnected-(IC2-PH6(OC2B)-Pad18)") (class "Default")
      (node (ref "IC2") (pin "18") (pinfunction "PH6(OC2B)_18") (pintype "bidirectional"))
    )
    (net (code "168") (name "unconnected-(IC2-PH7(T4)-Pad27)") (class "Default")
      (node (ref "IC2") (pin "27") (pinfunction "PH7(T4)_27") (pintype "bidirectional"))
    )
    (net (code "169") (name "unconnected-(IC2-PJ7-Pad79)") (class "Default")
      (node (ref "IC2") (pin "79") (pinfunction "PJ7_79") (pintype "bidirectional"))
    )
    (net (code "170") (name "unconnected-(LCD1-D0(SOD)-Pad7)") (class "Default")
      (node (ref "LCD1") (pin "7") (pinfunction "D0(SOD)_7") (pintype "no_connect"))
    )
    (net (code "171") (name "unconnected-(LCD1-D1-Pad8)") (class "Default")
      (node (ref "LCD1") (pin "8") (pinfunction "D1_8") (pintype "no_connect"))
    )
    (net (code "172") (name "unconnected-(LCD1-D2-Pad9)") (class "Default")
      (node (ref "LCD1") (pin "9") (pinfunction "D2_9") (pintype "no_connect"))
    )
    (net (code "173") (name "unconnected-(LCD1-D3-Pad10)") (class "Default")
      (node (ref "LCD1") (pin "10") (pinfunction "D3_10") (pintype "no_connect"))
    )
    (net (code "174") (name "unconnected-(LCD1-D4-Pad11)") (class "Default")
      (node (ref "LCD1") (pin "11") (pinfunction "D4_11") (pintype "no_connect"))
    )
    (net (code "175") (name "unconnected-(LCD1-D5-Pad12)") (class "Default")
      (node (ref "LCD1") (pin "12") (pinfunction "D5_12") (pintype "no_connect"))
    )
    (net (code "176") (name "unconnected-(LCD1-D6-Pad13)") (class "Default")
      (node (ref "LCD1") (pin "13") (pinfunction "D6_13") (pintype "no_connect"))
    )
    (net (code "177") (name "unconnected-(LCD1-D7-Pad14)") (class "Default")
      (node (ref "LCD1") (pin "14") (pinfunction "D7_14") (pintype "no_connect"))
    )
    (net (code "178") (name "unconnected-(LCD1-NC-Pad15)") (class "Default")
      (node (ref "LCD1") (pin "15") (pinfunction "NC_15") (pintype "no_connect"))
    )
    (net (code "179") (name "unconnected-(LCD1-RESET-Pad16)") (class "Default")
      (node (ref "LCD1") (pin "16") (pinfunction "RESET_16") (pintype "no_connect"))
    )
  )
)
